# project_X.net
KiCad netlist of a schematic drawn in EAGLE
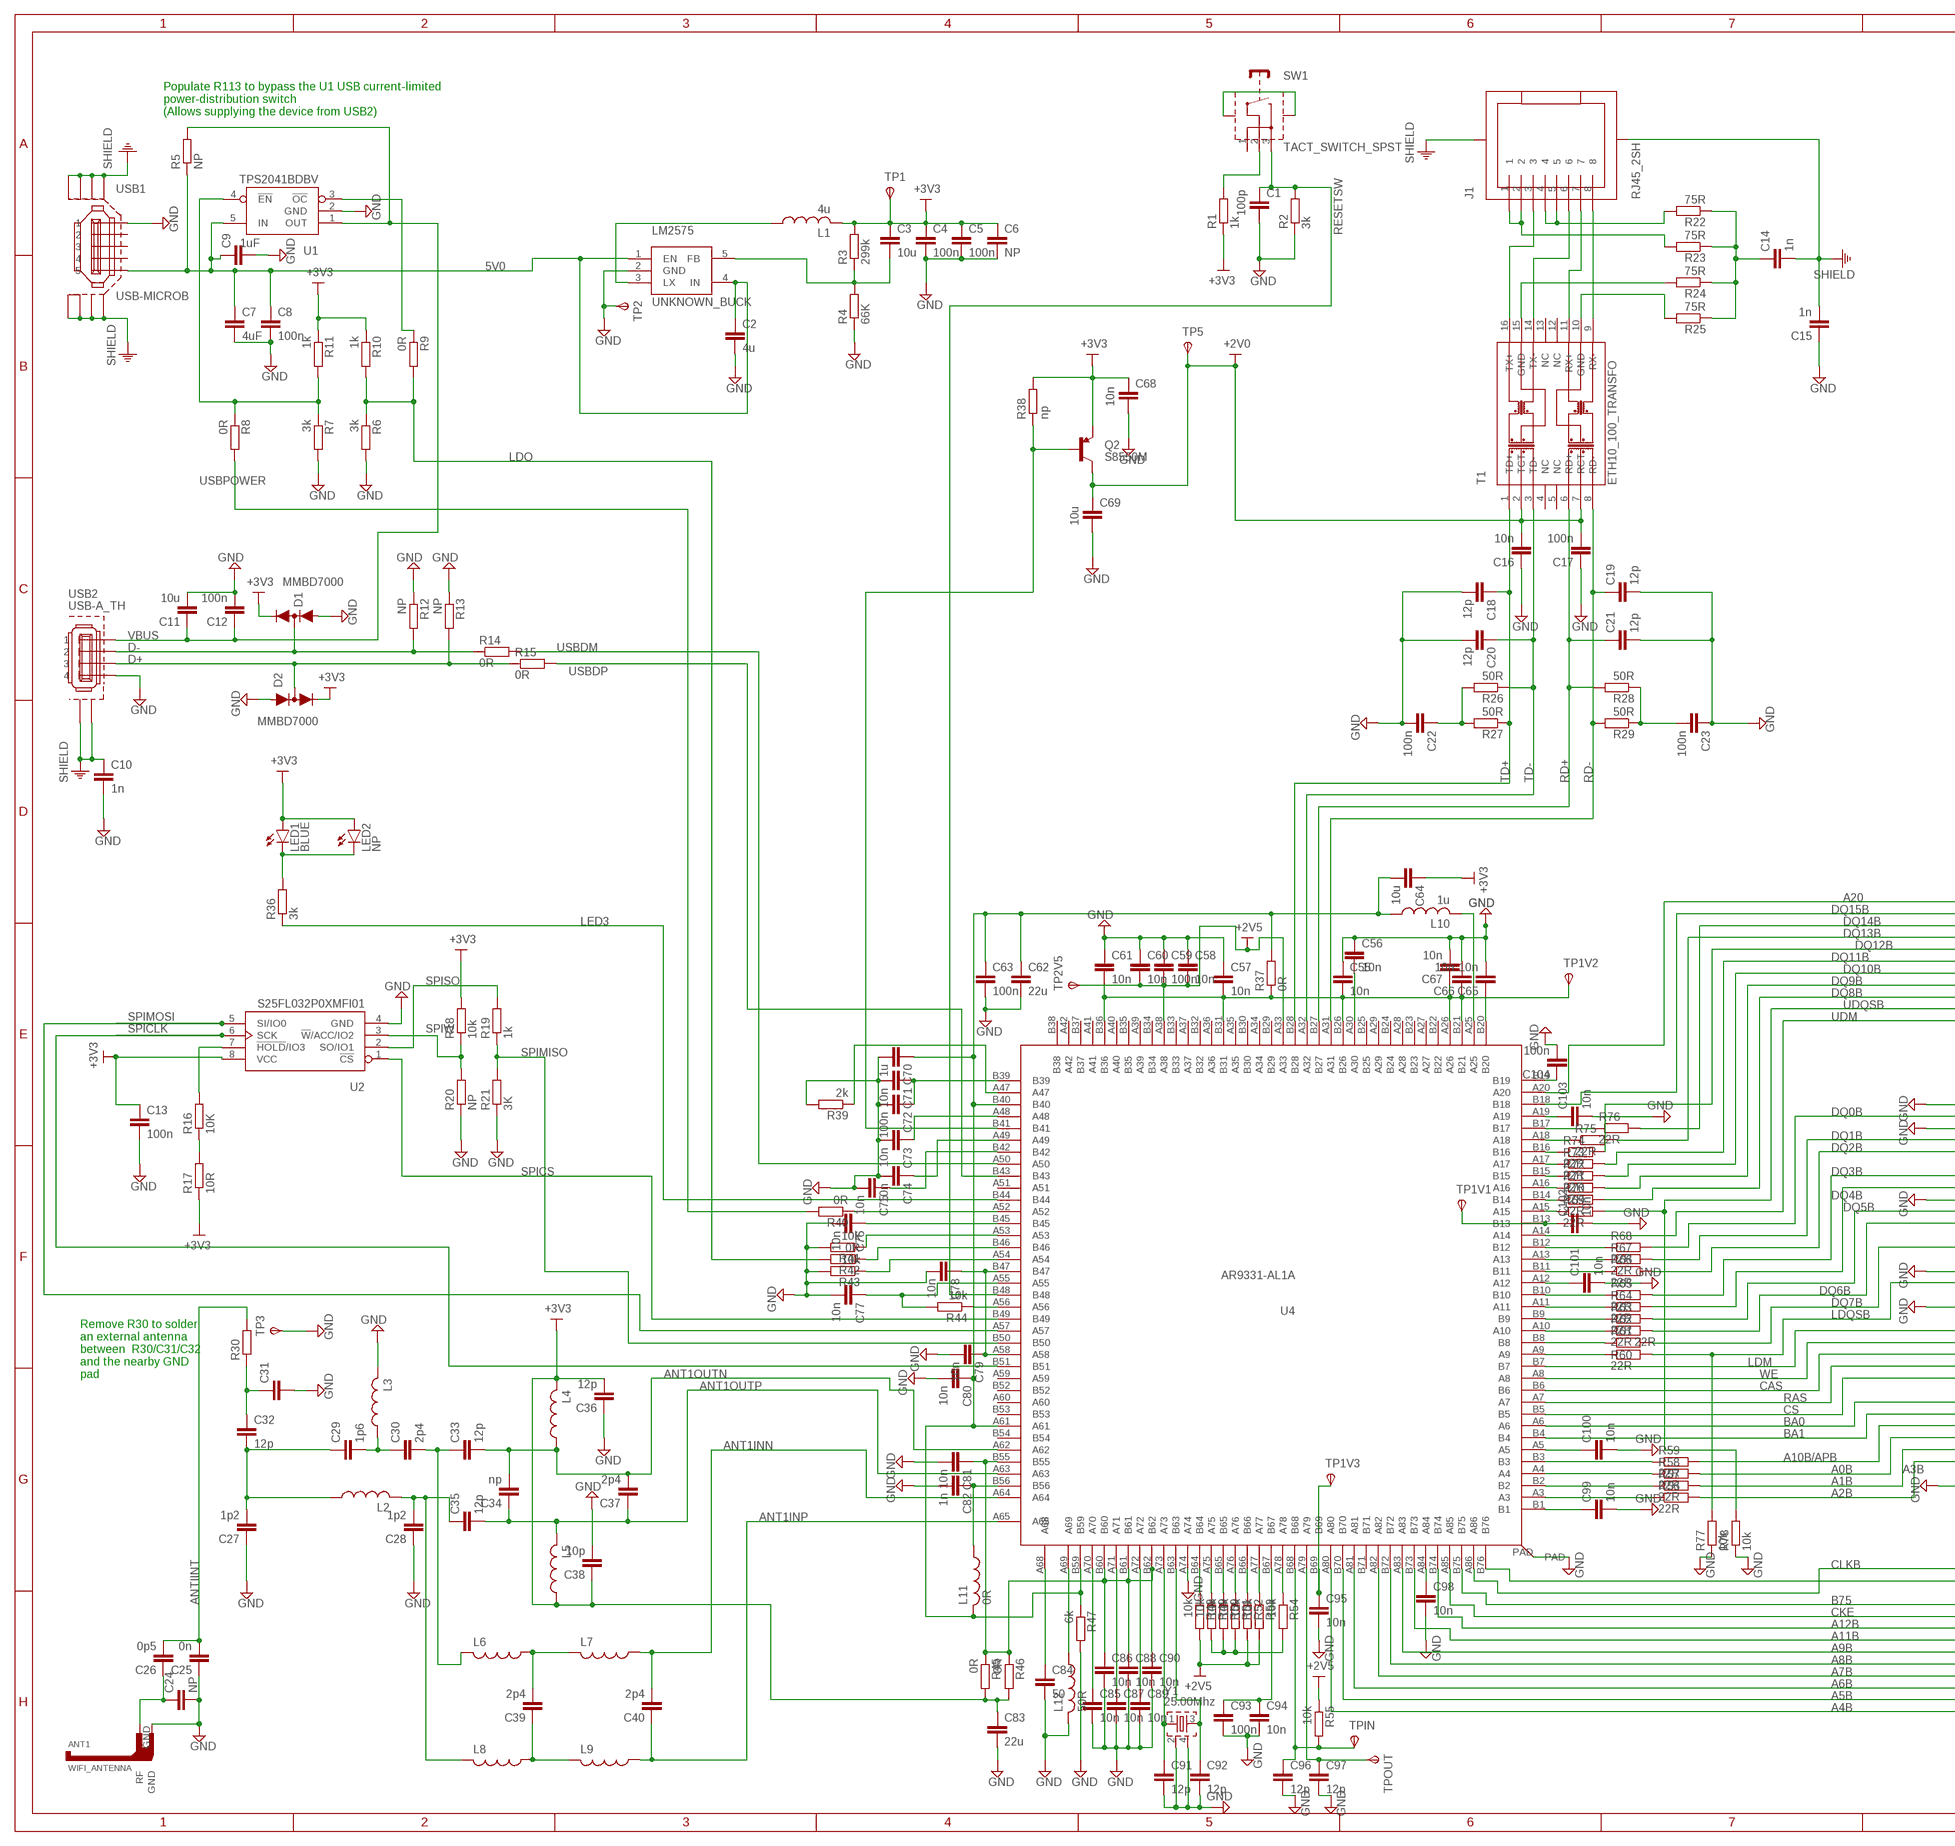
[diagram p0: schematic, sheet 1, part 1 of 2]
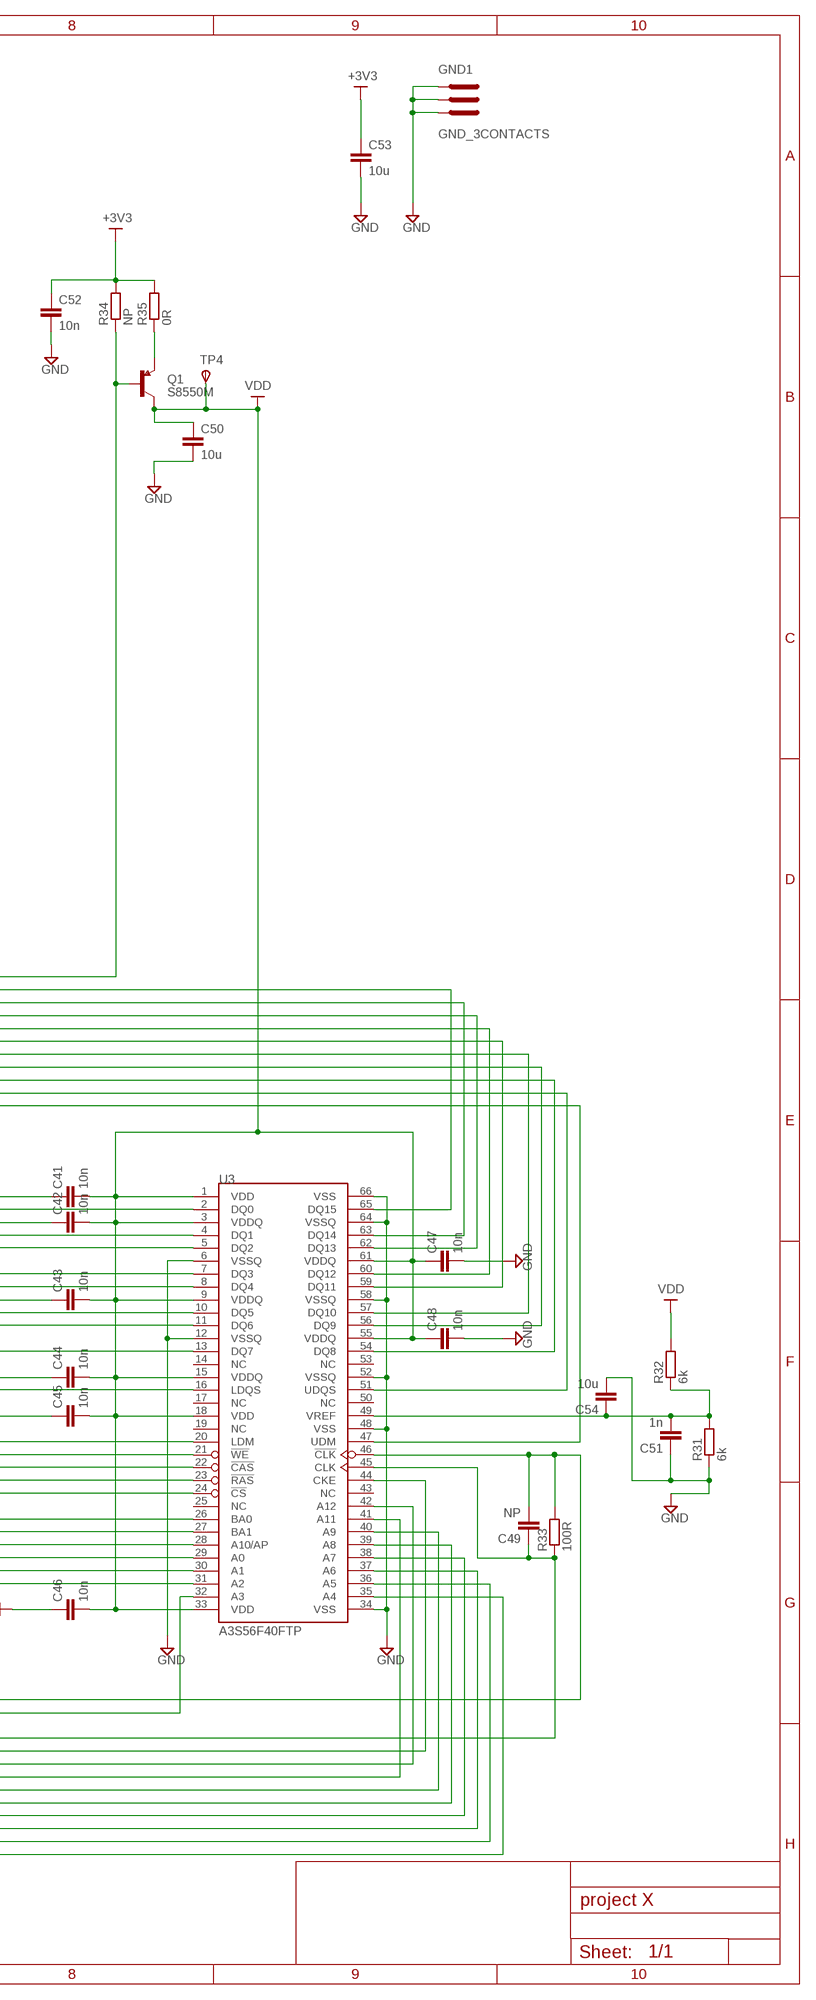
[diagram p1: schematic, sheet 1, part 2 of 2]

(export (version "E")
  (design (tool "Eeschema 10.0.6"))
  (components
    (comp (ref "ANT1")
      (value "WIFI_ANTENNA")
      (footprint "eagle-import:WIFI_ANTENNA")
      (libsource (lib "eagle-import") (part "WIFI_ANTENNA"))
    )
    (comp (ref "C1")
      (value "100p")
      (footprint "eagle-import:C0402")
      (libsource (lib "eagle-import") (part "CAP_0402"))
    )
    (comp (ref "C2")
      (value "4u")
      (footprint "eagle-import:C0603")
      (libsource (lib "eagle-import") (part "CAP_0603"))
    )
    (comp (ref "C3")
      (value "10u")
      (footprint "eagle-import:C0603")
      (libsource (lib "eagle-import") (part "CAP_0603"))
    )
    (comp (ref "C4")
      (value "100n")
      (footprint "eagle-import:C0603")
      (libsource (lib "eagle-import") (part "CAP_0603"))
    )
    (comp (ref "C5")
      (value "100n")
      (footprint "eagle-import:C0603")
      (libsource (lib "eagle-import") (part "CAP_0603"))
    )
    (comp (ref "C6")
      (value "NP")
      (footprint "eagle-import:C0603")
      (libsource (lib "eagle-import") (part "CAP_0603"))
    )
    (comp (ref "C7")
      (value "4uF")
      (footprint "eagle-import:C0603")
      (libsource (lib "eagle-import") (part "CAP_0603"))
    )
    (comp (ref "C8")
      (value "100n")
      (footprint "eagle-import:C0603")
      (libsource (lib "eagle-import") (part "CAP_0603"))
    )
    (comp (ref "C9")
      (value "1uF")
      (footprint "eagle-import:C0603")
      (libsource (lib "eagle-import") (part "CAP_0603"))
    )
    (comp (ref "C10")
      (value "1n")
      (footprint "eagle-import:C0603")
      (libsource (lib "eagle-import") (part "CAP_0603"))
    )
    (comp (ref "C11")
      (value "10u")
      (footprint "eagle-import:C0805")
      (libsource (lib "eagle-import") (part "CAP_0805"))
    )
    (comp (ref "C12")
      (value "100n")
      (footprint "eagle-import:C0805")
      (libsource (lib "eagle-import") (part "CAP_0805"))
    )
    (comp (ref "C13")
      (value "100n")
      (footprint "eagle-import:C0603")
      (libsource (lib "eagle-import") (part "CAP_0603"))
    )
    (comp (ref "C14")
      (value "1n")
      (footprint "eagle-import:C1206")
      (libsource (lib "eagle-import") (part "CAP_1206"))
    )
    (comp (ref "C15")
      (value "1n")
      (footprint "eagle-import:C1206")
      (libsource (lib "eagle-import") (part "CAP_1206"))
    )
    (comp (ref "C16")
      (value "10n")
      (footprint "eagle-import:C1206")
      (libsource (lib "eagle-import") (part "CAP_1206"))
    )
    (comp (ref "C17")
      (value "100n")
      (footprint "eagle-import:C1206")
      (libsource (lib "eagle-import") (part "CAP_1206"))
    )
    (comp (ref "C18")
      (value "12p")
      (footprint "eagle-import:C1206")
      (libsource (lib "eagle-import") (part "CAP_1206"))
    )
    (comp (ref "C19")
      (value "12p")
      (footprint "eagle-import:C1206")
      (libsource (lib "eagle-import") (part "CAP_1206"))
    )
    (comp (ref "C20")
      (value "12p")
      (footprint "eagle-import:C1206")
      (libsource (lib "eagle-import") (part "CAP_1206"))
    )
    (comp (ref "C21")
      (value "12p")
      (footprint "eagle-import:C1206")
      (libsource (lib "eagle-import") (part "CAP_1206"))
    )
    (comp (ref "C22")
      (value "100n")
      (footprint "eagle-import:C1206")
      (libsource (lib "eagle-import") (part "CAP_1206"))
    )
    (comp (ref "C23")
      (value "100n")
      (footprint "eagle-import:C1206")
      (libsource (lib "eagle-import") (part "CAP_1206"))
    )
    (comp (ref "C24")
      (value "NP")
      (footprint "eagle-import:C0603")
      (libsource (lib "eagle-import") (part "CAP_0603"))
    )
    (comp (ref "C25")
      (value "0n")
      (footprint "eagle-import:C0603")
      (libsource (lib "eagle-import") (part "CAP_0603"))
    )
    (comp (ref "C26")
      (value "0p5")
      (footprint "eagle-import:C0603")
      (libsource (lib "eagle-import") (part "CAP_0603"))
    )
    (comp (ref "C27")
      (value "1p2")
      (footprint "eagle-import:C0603")
      (libsource (lib "eagle-import") (part "CAP_0603"))
    )
    (comp (ref "C28")
      (value "1p2")
      (footprint "eagle-import:C0603")
      (libsource (lib "eagle-import") (part "CAP_0603"))
    )
    (comp (ref "C29")
      (value "1p6")
      (footprint "eagle-import:C0603")
      (libsource (lib "eagle-import") (part "CAP_0603"))
    )
    (comp (ref "C30")
      (value "2p4")
      (footprint "eagle-import:C0603")
      (libsource (lib "eagle-import") (part "CAP_0603"))
    )
    (comp (ref "C31")
      (value "CAP_0603")
      (footprint "eagle-import:C0603")
      (libsource (lib "eagle-import") (part "CAP_0603"))
    )
    (comp (ref "C32")
      (value "12p")
      (footprint "eagle-import:C0603")
      (libsource (lib "eagle-import") (part "CAP_0603"))
    )
    (comp (ref "C33")
      (value "12p")
      (footprint "eagle-import:C0603")
      (libsource (lib "eagle-import") (part "CAP_0603"))
    )
    (comp (ref "C34")
      (value "np")
      (footprint "eagle-import:C0603")
      (libsource (lib "eagle-import") (part "CAP_0603"))
    )
    (comp (ref "C35")
      (value "12p")
      (footprint "eagle-import:C0603")
      (libsource (lib "eagle-import") (part "CAP_0603"))
    )
    (comp (ref "C36")
      (value "12p")
      (footprint "eagle-import:C0603")
      (libsource (lib "eagle-import") (part "CAP_0603"))
    )
    (comp (ref "C37")
      (value "2p4")
      (footprint "eagle-import:C0603")
      (libsource (lib "eagle-import") (part "CAP_0603"))
    )
    (comp (ref "C38")
      (value "10p")
      (footprint "eagle-import:C0603")
      (libsource (lib "eagle-import") (part "CAP_0603"))
    )
    (comp (ref "C39")
      (value "2p4")
      (footprint "eagle-import:C0603")
      (libsource (lib "eagle-import") (part "CAP_0603"))
    )
    (comp (ref "C40")
      (value "2p4")
      (footprint "eagle-import:C0603")
      (libsource (lib "eagle-import") (part "CAP_0603"))
    )
    (comp (ref "C41")
      (value "10n")
      (footprint "eagle-import:C0603")
      (libsource (lib "eagle-import") (part "CAP_0603"))
    )
    (comp (ref "C42")
      (value "10n")
      (footprint "eagle-import:C0603")
      (libsource (lib "eagle-import") (part "CAP_0603"))
    )
    (comp (ref "C43")
      (value "10n")
      (footprint "eagle-import:C0603")
      (libsource (lib "eagle-import") (part "CAP_0603"))
    )
    (comp (ref "C44")
      (value "10n")
      (footprint "eagle-import:C0603")
      (libsource (lib "eagle-import") (part "CAP_0603"))
    )
    (comp (ref "C45")
      (value "10n")
      (footprint "eagle-import:C0603")
      (libsource (lib "eagle-import") (part "CAP_0603"))
    )
    (comp (ref "C46")
      (value "10n")
      (footprint "eagle-import:C0603")
      (libsource (lib "eagle-import") (part "CAP_0603"))
    )
    (comp (ref "C47")
      (value "10n")
      (footprint "eagle-import:C0603")
      (libsource (lib "eagle-import") (part "CAP_0603"))
    )
    (comp (ref "C48")
      (value "10n")
      (footprint "eagle-import:C0603")
      (libsource (lib "eagle-import") (part "CAP_0603"))
    )
    (comp (ref "C49")
      (value "NP")
      (footprint "eagle-import:C0603")
      (libsource (lib "eagle-import") (part "CAP_0603"))
    )
    (comp (ref "C50")
      (value "10u")
      (footprint "eagle-import:C0805")
      (libsource (lib "eagle-import") (part "CAP_0805"))
    )
    (comp (ref "C51")
      (value "1n")
      (footprint "eagle-import:C0603")
      (libsource (lib "eagle-import") (part "CAP_0603"))
    )
    (comp (ref "C52")
      (value "10n")
      (footprint "eagle-import:C0603")
      (libsource (lib "eagle-import") (part "CAP_0603"))
    )
    (comp (ref "C53")
      (value "10u")
      (footprint "eagle-import:C0805")
      (libsource (lib "eagle-import") (part "CAP_0805"))
    )
    (comp (ref "C54")
      (value "10u")
      (footprint "eagle-import:C0805")
      (libsource (lib "eagle-import") (part "CAP_0805"))
    )
    (comp (ref "C55")
      (value "10n")
      (footprint "eagle-import:C0805")
      (libsource (lib "eagle-import") (part "CAP_0805"))
    )
    (comp (ref "C56")
      (value "10n")
      (footprint "eagle-import:C0805")
      (libsource (lib "eagle-import") (part "CAP_0805"))
    )
    (comp (ref "C57")
      (value "10n")
      (footprint "eagle-import:C0805")
      (libsource (lib "eagle-import") (part "CAP_0805"))
    )
    (comp (ref "C58")
      (value "10n")
      (footprint "eagle-import:C0805")
      (libsource (lib "eagle-import") (part "CAP_0805"))
    )
    (comp (ref "C59")
      (value "100n")
      (footprint "eagle-import:C0805")
      (libsource (lib "eagle-import") (part "CAP_0805"))
    )
    (comp (ref "C60")
      (value "10n")
      (footprint "eagle-import:C0805")
      (libsource (lib "eagle-import") (part "CAP_0805"))
    )
    (comp (ref "C61")
      (value "10n")
      (footprint "eagle-import:C0805")
      (libsource (lib "eagle-import") (part "CAP_0805"))
    )
    (comp (ref "C62")
      (value "22u")
      (footprint "eagle-import:C0805")
      (libsource (lib "eagle-import") (part "CAP_0805"))
    )
    (comp (ref "C63")
      (value "100n")
      (footprint "eagle-import:C0805")
      (libsource (lib "eagle-import") (part "CAP_0805"))
    )
    (comp (ref "C64")
      (value "10u")
      (footprint "eagle-import:C0805")
      (libsource (lib "eagle-import") (part "CAP_0805"))
    )
    (comp (ref "C65")
      (value "10n")
      (footprint "eagle-import:C0805")
      (libsource (lib "eagle-import") (part "CAP_0805"))
    )
    (comp (ref "C66")
      (value "10n")
      (footprint "eagle-import:C0805")
      (libsource (lib "eagle-import") (part "CAP_0805"))
    )
    (comp (ref "C67")
      (value "10n")
      (footprint "eagle-import:C0805")
      (libsource (lib "eagle-import") (part "CAP_0805"))
    )
    (comp (ref "C68")
      (value "10n")
      (footprint "eagle-import:C0402")
      (libsource (lib "eagle-import") (part "CAP_0402"))
    )
    (comp (ref "C69")
      (value "10u")
      (footprint "eagle-import:C0402")
      (libsource (lib "eagle-import") (part "CAP_0402"))
    )
    (comp (ref "C70")
      (value "1u")
      (footprint "eagle-import:C0603")
      (libsource (lib "eagle-import") (part "CAP_0603"))
    )
    (comp (ref "C71")
      (value "10n")
      (footprint "eagle-import:C0603")
      (libsource (lib "eagle-import") (part "CAP_0603"))
    )
    (comp (ref "C72")
      (value "100n")
      (footprint "eagle-import:C0603")
      (libsource (lib "eagle-import") (part "CAP_0603"))
    )
    (comp (ref "C73")
      (value "10n")
      (footprint "eagle-import:C0603")
      (libsource (lib "eagle-import") (part "CAP_0603"))
    )
    (comp (ref "C74")
      (value "10n")
      (footprint "eagle-import:C0603")
      (libsource (lib "eagle-import") (part "CAP_0603"))
    )
    (comp (ref "C75")
      (value "10n")
      (footprint "eagle-import:C0603")
      (libsource (lib "eagle-import") (part "CAP_0603"))
    )
    (comp (ref "C76")
      (value "10n")
      (footprint "eagle-import:C0603")
      (libsource (lib "eagle-import") (part "CAP_0603"))
    )
    (comp (ref "C77")
      (value "10n")
      (footprint "eagle-import:C0603")
      (libsource (lib "eagle-import") (part "CAP_0603"))
    )
    (comp (ref "C78")
      (value "10n")
      (footprint "eagle-import:C0603")
      (libsource (lib "eagle-import") (part "CAP_0603"))
    )
    (comp (ref "C79")
      (value "10n")
      (footprint "eagle-import:C0603")
      (libsource (lib "eagle-import") (part "CAP_0603"))
    )
    (comp (ref "C80")
      (value "10n")
      (footprint "eagle-import:C0603")
      (libsource (lib "eagle-import") (part "CAP_0603"))
    )
    (comp (ref "C81")
      (value "10n")
      (footprint "eagle-import:C0603")
      (libsource (lib "eagle-import") (part "CAP_0603"))
    )
    (comp (ref "C82")
      (value "1n")
      (footprint "eagle-import:C0603")
      (libsource (lib "eagle-import") (part "CAP_0603"))
    )
    (comp (ref "C83")
      (value "22u")
      (footprint "eagle-import:C0603")
      (libsource (lib "eagle-import") (part "CAP_0603"))
    )
    (comp (ref "C84")
      (value "50")
      (footprint "eagle-import:C0603")
      (libsource (lib "eagle-import") (part "CAP_0603"))
    )
    (comp (ref "C85")
      (value "10n")
      (footprint "eagle-import:C0603")
      (libsource (lib "eagle-import") (part "CAP_0603"))
    )
    (comp (ref "C86")
      (value "10n")
      (footprint "eagle-import:C0603")
      (libsource (lib "eagle-import") (part "CAP_0603"))
    )
    (comp (ref "C87")
      (value "10n")
      (footprint "eagle-import:C0603")
      (libsource (lib "eagle-import") (part "CAP_0603"))
    )
    (comp (ref "C88")
      (value "10n")
      (footprint "eagle-import:C0603")
      (libsource (lib "eagle-import") (part "CAP_0603"))
    )
    (comp (ref "C89")
      (value "10n")
      (footprint "eagle-import:C0603")
      (libsource (lib "eagle-import") (part "CAP_0603"))
    )
    (comp (ref "C90")
      (value "10n")
      (footprint "eagle-import:C0603")
      (libsource (lib "eagle-import") (part "CAP_0603"))
    )
    (comp (ref "C91")
      (value "12p")
      (footprint "eagle-import:C0603")
      (libsource (lib "eagle-import") (part "CAP_0603"))
    )
    (comp (ref "C92")
      (value "12p")
      (footprint "eagle-import:C0603")
      (libsource (lib "eagle-import") (part "CAP_0603"))
    )
    (comp (ref "C93")
      (value "100n")
      (footprint "eagle-import:C0603")
      (libsource (lib "eagle-import") (part "CAP_0603"))
    )
    (comp (ref "C94")
      (value "10n")
      (footprint "eagle-import:C0603")
      (libsource (lib "eagle-import") (part "CAP_0603"))
    )
    (comp (ref "C95")
      (value "10n")
      (footprint "eagle-import:C0603")
      (libsource (lib "eagle-import") (part "CAP_0603"))
    )
    (comp (ref "C96")
      (value "12p")
      (footprint "eagle-import:C0603")
      (libsource (lib "eagle-import") (part "CAP_0603"))
    )
    (comp (ref "C97")
      (value "12p")
      (footprint "eagle-import:C0603")
      (libsource (lib "eagle-import") (part "CAP_0603"))
    )
    (comp (ref "C98")
      (value "10n")
      (footprint "eagle-import:C0603")
      (libsource (lib "eagle-import") (part "CAP_0603"))
    )
    (comp (ref "C99")
      (value "10n")
      (footprint "eagle-import:C0603")
      (libsource (lib "eagle-import") (part "CAP_0603"))
    )
    (comp (ref "C100")
      (value "10n")
      (footprint "eagle-import:C0603")
      (libsource (lib "eagle-import") (part "CAP_0603"))
    )
    (comp (ref "C101")
      (value "10n")
      (footprint "eagle-import:C0603")
      (libsource (lib "eagle-import") (part "CAP_0603"))
    )
    (comp (ref "C102")
      (value "10n")
      (footprint "eagle-import:C0603")
      (libsource (lib "eagle-import") (part "CAP_0603"))
    )
    (comp (ref "C103")
      (value "10n")
      (footprint "eagle-import:C0603")
      (libsource (lib "eagle-import") (part "CAP_0603"))
    )
    (comp (ref "C104")
      (value "100n")
      (footprint "eagle-import:C0603")
      (libsource (lib "eagle-import") (part "CAP_0603"))
    )
    (comp (ref "D1")
      (value "MMBD7000")
      (footprint "eagle-import:SOT23-3")
      (libsource (lib "eagle-import") (part "MMBD7000"))
    )
    (comp (ref "D2")
      (value "MMBD7000")
      (footprint "eagle-import:SOT23-3")
      (libsource (lib "eagle-import") (part "MMBD7000"))
    )
    (comp (ref "GND1")
      (value "GND_3CONTACTS")
      (footprint "eagle-import:GND_3CONTACT")
      (libsource (lib "eagle-import") (part "GND_3CONTACTS"))
    )
    (comp (ref "J1")
      (value "RJ45_2SH")
      (footprint "eagle-import:RJ45_LP_RA_SMT")
      (libsource (lib "eagle-import") (part "RJ45_2SH"))
    )
    (comp (ref "L1")
      (value "4u")
      (footprint "eagle-import:L0402")
      (libsource (lib "eagle-import") (part "IND_0402"))
    )
    (comp (ref "L2")
      (value "IND_0402")
      (footprint "eagle-import:L0402")
      (libsource (lib "eagle-import") (part "IND_0402"))
    )
    (comp (ref "L3")
      (value "IND_0402")
      (footprint "eagle-import:L0402")
      (libsource (lib "eagle-import") (part "IND_0402"))
    )
    (comp (ref "L4")
      (value "IND_0402")
      (footprint "eagle-import:L0402")
      (libsource (lib "eagle-import") (part "IND_0402"))
    )
    (comp (ref "L5")
      (value "IND_0402")
      (footprint "eagle-import:L0402")
      (libsource (lib "eagle-import") (part "IND_0402"))
    )
    (comp (ref "L6")
      (value "IND_0402")
      (footprint "eagle-import:L0402")
      (libsource (lib "eagle-import") (part "IND_0402"))
    )
    (comp (ref "L7")
      (value "IND_0402")
      (footprint "eagle-import:L0402")
      (libsource (lib "eagle-import") (part "IND_0402"))
    )
    (comp (ref "L8")
      (value "IND_0402")
      (footprint "eagle-import:L0402")
      (libsource (lib "eagle-import") (part "IND_0402"))
    )
    (comp (ref "L9")
      (value "IND_0402")
      (footprint "eagle-import:L0402")
      (libsource (lib "eagle-import") (part "IND_0402"))
    )
    (comp (ref "L10")
      (value "1u")
      (footprint "eagle-import:L1008")
      (libsource (lib "eagle-import") (part "IND_1008"))
    )
    (comp (ref "L11")
      (value "0R")
      (footprint "eagle-import:L0402")
      (libsource (lib "eagle-import") (part "IND_0402"))
    )
    (comp (ref "L12")
      (value "50R")
      (footprint "eagle-import:L0402")
      (libsource (lib "eagle-import") (part "IND_0402"))
    )
    (comp (ref "LED1")
      (value "BLUE")
      (footprint "eagle-import:LED3MM")
      (libsource (lib "eagle-import") (part "LED_3MM"))
    )
    (comp (ref "LED2")
      (value "NP")
      (footprint "eagle-import:LED3MM")
      (libsource (lib "eagle-import") (part "LED_3MM"))
    )
    (comp (ref "LM2575")
      (value "UNKNOWN_BUCK")
      (footprint "eagle-import:SOT23-5")
      (libsource (lib "eagle-import") (part "UNKNOWN_BUCK"))
    )
    (comp (ref "Q1")
      (value "S8550M")
      (footprint "eagle-import:SOT23-3")
      (libsource (lib "eagle-import") (part "TRANSISTOR_PNP"))
    )
    (comp (ref "Q2")
      (value "S8550M")
      (footprint "eagle-import:SOT23-3")
      (libsource (lib "eagle-import") (part "TRANSISTOR_PNP"))
    )
    (comp (ref "R1")
      (value "1k")
      (footprint "eagle-import:R0402")
      (libsource (lib "eagle-import") (part "RES_0402"))
    )
    (comp (ref "R2")
      (value "3k")
      (footprint "eagle-import:R0402")
      (libsource (lib "eagle-import") (part "RES_0402"))
    )
    (comp (ref "R3")
      (value "299k")
      (footprint "eagle-import:R0603")
      (libsource (lib "eagle-import") (part "RES_0603"))
    )
    (comp (ref "R4")
      (value "66K")
      (footprint "eagle-import:R0603")
      (libsource (lib "eagle-import") (part "RES_0603"))
    )
    (comp (ref "R5")
      (value "NP")
      (footprint "eagle-import:R0603")
      (libsource (lib "eagle-import") (part "RES_0603"))
    )
    (comp (ref "R6")
      (value "3k")
      (footprint "eagle-import:R0603")
      (libsource (lib "eagle-import") (part "RES_0603"))
    )
    (comp (ref "R7")
      (value "3k")
      (footprint "eagle-import:R0603")
      (libsource (lib "eagle-import") (part "RES_0603"))
    )
    (comp (ref "R8")
      (value "0R")
      (footprint "eagle-import:R0603")
      (libsource (lib "eagle-import") (part "RES_0603"))
    )
    (comp (ref "R9")
      (value "0R")
      (footprint "eagle-import:R0603")
      (libsource (lib "eagle-import") (part "RES_0603"))
    )
    (comp (ref "R10")
      (value "1k")
      (footprint "eagle-import:R0603")
      (libsource (lib "eagle-import") (part "RES_0603"))
    )
    (comp (ref "R11")
      (value "1k")
      (footprint "eagle-import:R0603")
      (libsource (lib "eagle-import") (part "RES_0603"))
    )
    (comp (ref "R12")
      (value "NP")
      (footprint "eagle-import:R0603")
      (libsource (lib "eagle-import") (part "RES_0603"))
    )
    (comp (ref "R13")
      (value "NP")
      (footprint "eagle-import:R0603")
      (libsource (lib "eagle-import") (part "RES_0603"))
    )
    (comp (ref "R14")
      (value "0R")
      (footprint "eagle-import:R0603")
      (libsource (lib "eagle-import") (part "RES_0603"))
    )
    (comp (ref "R15")
      (value "0R")
      (footprint "eagle-import:R0603")
      (libsource (lib "eagle-import") (part "RES_0603"))
    )
    (comp (ref "R16")
      (value "10K")
      (footprint "eagle-import:R0603")
      (libsource (lib "eagle-import") (part "RES_0603"))
    )
    (comp (ref "R17")
      (value "10R")
      (footprint "eagle-import:R0603")
      (libsource (lib "eagle-import") (part "RES_0603"))
    )
    (comp (ref "R18")
      (value "10k")
      (footprint "eagle-import:R0603")
      (libsource (lib "eagle-import") (part "RES_0603"))
    )
    (comp (ref "R19")
      (value "1k")
      (footprint "eagle-import:R0603")
      (libsource (lib "eagle-import") (part "RES_0603"))
    )
    (comp (ref "R20")
      (value "NP")
      (footprint "eagle-import:R0603")
      (libsource (lib "eagle-import") (part "RES_0603"))
    )
    (comp (ref "R21")
      (value "3K")
      (footprint "eagle-import:R0603")
      (libsource (lib "eagle-import") (part "RES_0603"))
    )
    (comp (ref "R22")
      (value "75R")
      (footprint "eagle-import:R0402")
      (libsource (lib "eagle-import") (part "RES_0402"))
    )
    (comp (ref "R23")
      (value "75R")
      (footprint "eagle-import:R0402")
      (libsource (lib "eagle-import") (part "RES_0402"))
    )
    (comp (ref "R24")
      (value "75R")
      (footprint "eagle-import:R0402")
      (libsource (lib "eagle-import") (part "RES_0402"))
    )
    (comp (ref "R25")
      (value "75R")
      (footprint "eagle-import:R0402")
      (libsource (lib "eagle-import") (part "RES_0402"))
    )
    (comp (ref "R26")
      (value "50R")
      (footprint "eagle-import:R0402")
      (libsource (lib "eagle-import") (part "RES_0402"))
    )
    (comp (ref "R27")
      (value "50R")
      (footprint "eagle-import:R0402")
      (libsource (lib "eagle-import") (part "RES_0402"))
    )
    (comp (ref "R28")
      (value "50R")
      (footprint "eagle-import:R0402")
      (libsource (lib "eagle-import") (part "RES_0402"))
    )
    (comp (ref "R29")
      (value "50R")
      (footprint "eagle-import:R0402")
      (libsource (lib "eagle-import") (part "RES_0402"))
    )
    (comp (ref "R30")
      (value "RES_0603")
      (footprint "eagle-import:R0603")
      (libsource (lib "eagle-import") (part "RES_0603"))
    )
    (comp (ref "R31")
      (value "6k")
      (footprint "eagle-import:R0603")
      (libsource (lib "eagle-import") (part "RES_0603"))
    )
    (comp (ref "R32")
      (value "6k")
      (footprint "eagle-import:R0603")
      (libsource (lib "eagle-import") (part "RES_0603"))
    )
    (comp (ref "R33")
      (value "100R")
      (footprint "eagle-import:R0603")
      (libsource (lib "eagle-import") (part "RES_0603"))
    )
    (comp (ref "R34")
      (value "NP")
      (footprint "eagle-import:R0603")
      (libsource (lib "eagle-import") (part "RES_0603"))
    )
    (comp (ref "R35")
      (value "0R")
      (footprint "eagle-import:R0603")
      (libsource (lib "eagle-import") (part "RES_0603"))
    )
    (comp (ref "R36")
      (value "3k")
      (footprint "eagle-import:R0603")
      (libsource (lib "eagle-import") (part "RES_0603"))
    )
    (comp (ref "R37")
      (value "0R")
      (footprint "eagle-import:R0603")
      (libsource (lib "eagle-import") (part "RES_0603"))
    )
    (comp (ref "R38")
      (value "np")
      (footprint "eagle-import:R0603")
      (libsource (lib "eagle-import") (part "RES_0603"))
    )
    (comp (ref "R39")
      (value "2k")
      (footprint "eagle-import:R0603")
      (libsource (lib "eagle-import") (part "RES_0603"))
    )
    (comp (ref "R40")
      (value "0R")
      (footprint "eagle-import:R0603")
      (libsource (lib "eagle-import") (part "RES_0603"))
    )
    (comp (ref "R41")
      (value "10k")
      (footprint "eagle-import:R0603")
      (libsource (lib "eagle-import") (part "RES_0603"))
    )
    (comp (ref "R42")
      (value "0R")
      (footprint "eagle-import:R0603")
      (libsource (lib "eagle-import") (part "RES_0603"))
    )
    (comp (ref "R43")
      (value "10k")
      (footprint "eagle-import:R0603")
      (libsource (lib "eagle-import") (part "RES_0603"))
    )
    (comp (ref "R44")
      (value "10k")
      (footprint "eagle-import:R0603")
      (libsource (lib "eagle-import") (part "RES_0603"))
    )
    (comp (ref "R45")
      (value "0R")
      (footprint "eagle-import:R0603")
      (libsource (lib "eagle-import") (part "RES_0603"))
    )
    (comp (ref "R46")
      (value "0R")
      (footprint "eagle-import:R0603")
      (libsource (lib "eagle-import") (part "RES_0603"))
    )
    (comp (ref "R47")
      (value "6k")
      (footprint "eagle-import:R0603")
      (libsource (lib "eagle-import") (part "RES_0603"))
    )
    (comp (ref "R48")
      (value "10k")
      (footprint "eagle-import:R0603")
      (libsource (lib "eagle-import") (part "RES_0603"))
    )
    (comp (ref "R49")
      (value "10k")
      (footprint "eagle-import:R0603")
      (libsource (lib "eagle-import") (part "RES_0603"))
    )
    (comp (ref "R50")
      (value "10k")
      (footprint "eagle-import:R0603")
      (libsource (lib "eagle-import") (part "RES_0603"))
    )
    (comp (ref "R51")
      (value "10k")
      (footprint "eagle-import:R0603")
      (libsource (lib "eagle-import") (part "RES_0603"))
    )
    (comp (ref "R52")
      (value "10k")
      (footprint "eagle-import:R0603")
      (libsource (lib "eagle-import") (part "RES_0603"))
    )
    (comp (ref "R53")
      (value "10k")
      (footprint "eagle-import:R0603")
      (libsource (lib "eagle-import") (part "RES_0603"))
    )
    (comp (ref "R54")
      (value "10k")
      (footprint "eagle-import:R0603")
      (libsource (lib "eagle-import") (part "RES_0603"))
    )
    (comp (ref "R55")
      (value "10k")
      (footprint "eagle-import:R0603")
      (libsource (lib "eagle-import") (part "RES_0603"))
    )
    (comp (ref "R56")
      (value "22R")
      (footprint "eagle-import:R0603")
      (libsource (lib "eagle-import") (part "RES_0603"))
    )
    (comp (ref "R57")
      (value "22R")
      (footprint "eagle-import:R0603")
      (libsource (lib "eagle-import") (part "RES_0603"))
    )
    (comp (ref "R58")
      (value "22R")
      (footprint "eagle-import:R0603")
      (libsource (lib "eagle-import") (part "RES_0603"))
    )
    (comp (ref "R59")
      (value "22R")
      (footprint "eagle-import:R0603")
      (libsource (lib "eagle-import") (part "RES_0603"))
    )
    (comp (ref "R60")
      (value "22R")
      (footprint "eagle-import:R0603")
      (libsource (lib "eagle-import") (part "RES_0603"))
    )
    (comp (ref "R61")
      (value "22R")
      (footprint "eagle-import:R0603")
      (libsource (lib "eagle-import") (part "RES_0603"))
    )
    (comp (ref "R62")
      (value "22R")
      (footprint "eagle-import:R0603")
      (libsource (lib "eagle-import") (part "RES_0603"))
    )
    (comp (ref "R63")
      (value "22R")
      (footprint "eagle-import:R0603")
      (libsource (lib "eagle-import") (part "RES_0603"))
    )
    (comp (ref "R64")
      (value "22R")
      (footprint "eagle-import:R0603")
      (libsource (lib "eagle-import") (part "RES_0603"))
    )
    (comp (ref "R65")
      (value "22R")
      (footprint "eagle-import:R0603")
      (libsource (lib "eagle-import") (part "RES_0603"))
    )
    (comp (ref "R66")
      (value "22R")
      (footprint "eagle-import:R0603")
      (libsource (lib "eagle-import") (part "RES_0603"))
    )
    (comp (ref "R67")
      (value "22R")
      (footprint "eagle-import:R0603")
      (libsource (lib "eagle-import") (part "RES_0603"))
    )
    (comp (ref "R68")
      (value "22R")
      (footprint "eagle-import:R0603")
      (libsource (lib "eagle-import") (part "RES_0603"))
    )
    (comp (ref "R69")
      (value "22R")
      (footprint "eagle-import:R0603")
      (libsource (lib "eagle-import") (part "RES_0603"))
    )
    (comp (ref "R70")
      (value "22R")
      (footprint "eagle-import:R0603")
      (libsource (lib "eagle-import") (part "RES_0603"))
    )
    (comp (ref "R71")
      (value "22R")
      (footprint "eagle-import:R0603")
      (libsource (lib "eagle-import") (part "RES_0603"))
    )
    (comp (ref "R72")
      (value "22R")
      (footprint "eagle-import:R0603")
      (libsource (lib "eagle-import") (part "RES_0603"))
    )
    (comp (ref "R73")
      (value "22R")
      (footprint "eagle-import:R0603")
      (libsource (lib "eagle-import") (part "RES_0603"))
    )
    (comp (ref "R74")
      (value "22R")
      (footprint "eagle-import:R0603")
      (libsource (lib "eagle-import") (part "RES_0603"))
    )
    (comp (ref "R75")
      (value "22R")
      (footprint "eagle-import:R0603")
      (libsource (lib "eagle-import") (part "RES_0603"))
    )
    (comp (ref "R76")
      (value "22R")
      (footprint "eagle-import:R0603")
      (libsource (lib "eagle-import") (part "RES_0603"))
    )
    (comp (ref "R77")
      (value "10k")
      (footprint "eagle-import:R0603")
      (libsource (lib "eagle-import") (part "RES_0603"))
    )
    (comp (ref "R78")
      (value "10k")
      (footprint "eagle-import:R0603")
      (libsource (lib "eagle-import") (part "RES_0603"))
    )
    (comp (ref "SW1")
      (value "TACT_SWITCH_SPST")
      (footprint "eagle-import:TACT_SWITCH_SPST_RA_SMT")
      (libsource (lib "eagle-import") (part "TACT_SWITCH_SPST"))
    )
    (comp (ref "T1")
      (value "ETH10_100_TRANSFO")
      (footprint "eagle-import:H1601CG")
      (libsource (lib "eagle-import") (part "ETH10_100_TRANSFO"))
    )
    (comp (ref "TP1")
      (value "TEST_PAD")
      (footprint "eagle-import:TEST_PAD")
      (libsource (lib "eagle-import") (part "TEST_PAD"))
    )
    (comp (ref "TP1V1")
      (value "TEST_PAD")
      (footprint "eagle-import:TEST_PAD")
      (libsource (lib "eagle-import") (part "TEST_PAD"))
    )
    (comp (ref "TP1V2")
      (value "TEST_PAD")
      (footprint "eagle-import:TEST_PAD")
      (libsource (lib "eagle-import") (part "TEST_PAD"))
    )
    (comp (ref "TP1V3")
      (value "TEST_PAD")
      (footprint "eagle-import:TEST_PAD")
      (libsource (lib "eagle-import") (part "TEST_PAD"))
    )
    (comp (ref "TP2")
      (value "TEST_PAD")
      (footprint "eagle-import:TEST_PAD")
      (libsource (lib "eagle-import") (part "TEST_PAD"))
    )
    (comp (ref "TP2V5")
      (value "TEST_PAD")
      (footprint "eagle-import:TEST_PAD")
      (libsource (lib "eagle-import") (part "TEST_PAD"))
    )
    (comp (ref "TP3")
      (value "TEST_PAD")
      (footprint "eagle-import:TEST_PAD")
      (libsource (lib "eagle-import") (part "TEST_PAD"))
    )
    (comp (ref "TP4")
      (value "TEST_PAD")
      (footprint "eagle-import:TEST_PAD")
      (libsource (lib "eagle-import") (part "TEST_PAD"))
    )
    (comp (ref "TP5")
      (value "TEST_PAD")
      (footprint "eagle-import:TEST_PAD")
      (libsource (lib "eagle-import") (part "TEST_PAD"))
    )
    (comp (ref "TPIN")
      (value "TEST_PAD")
      (footprint "eagle-import:TEST_PAD")
      (libsource (lib "eagle-import") (part "TEST_PAD"))
    )
    (comp (ref "TPOUT")
      (value "TEST_PAD")
      (footprint "eagle-import:TEST_PAD")
      (libsource (lib "eagle-import") (part "TEST_PAD"))
    )
    (comp (ref "U1")
      (value "TPS2041BDBV")
      (footprint "eagle-import:SOT23-5")
      (libsource (lib "eagle-import") (part "TPS2041BDBV"))
    )
    (comp (ref "U2")
      (value "S25FL032P0XMFI01")
      (footprint "eagle-import:SOP8")
      (libsource (lib "eagle-import") (part "S25FLP0XMFI01032"))
    )
    (comp (ref "U3")
      (value "A3S56F40FTP")
      (footprint "eagle-import:TSOP66")
      (libsource (lib "eagle-import") (part "A3S56FTPF40"))
    )
    (comp (ref "U4")
      (value "AR9331-AL1A")
      (footprint "eagle-import:DRMLF164")
      (libsource (lib "eagle-import") (part "AR9331-AL1A"))
    )
    (comp (ref "USB1")
      (value "USB-MICROB")
      (footprint "eagle-import:USB-MICROB")
      (libsource (lib "eagle-import") (part "USB-MICROB"))
    )
    (comp (ref "USB2")
      (value "USB-A_TH")
      (footprint "eagle-import:USB-A_TH")
      (libsource (lib "eagle-import") (part "USB-A_TH"))
    )
    (comp (ref "Y1")
      (value "25.00Mhz")
      (footprint "eagle-import:CRYSTAL_32_25")
      (libsource (lib "eagle-import") (part "CRYSTAL_2SHIELD"))
    )
  )
  (nets
    (net (code "1") (name "+2V0") (class "Default")
      (node (ref "C16") (pin "2") (pinfunction "2_2") (pintype "passive"))
      (node (ref "C17") (pin "2") (pinfunction "2_2") (pintype "passive"))
      (node (ref "C69") (pin "1") (pinfunction "1_1") (pintype "passive"))
      (node (ref "Q2") (pin "3") (pinfunction "C_3") (pintype "passive"))
      (node (ref "T1") (pin "2") (pinfunction "TCT_2") (pintype "passive"))
      (node (ref "T1") (pin "7") (pinfunction "RCT_7") (pintype "passive"))
      (node (ref "TP5") (pin "1") (pinfunction "PP_1") (pintype "input"))
    )
    (net (code "2") (name "+2V5") (class "Default")
      (node (ref "C58") (pin "2") (pinfunction "2_2") (pintype "passive"))
      (node (ref "C59") (pin "2") (pinfunction "2_2") (pintype "passive"))
      (node (ref "C60") (pin "2") (pinfunction "2_2") (pintype "passive"))
      (node (ref "R48") (pin "2") (pinfunction "2_2") (pintype "passive"))
      (node (ref "R52") (pin "2") (pinfunction "2_2") (pintype "passive"))
      (node (ref "R53") (pin "2") (pinfunction "2_2") (pintype "passive"))
      (node (ref "R55") (pin "1") (pinfunction "1_1") (pintype "passive"))
      (node (ref "TP2V5") (pin "1") (pinfunction "PP_1") (pintype "input"))
      (node (ref "U4") (pin "A33") (pinfunction "A33_A33") (pintype "bidirectional"))
      (node (ref "U4") (pin "A38") (pinfunction "A38_A38") (pintype "bidirectional"))
    )
    (net (code "3") (name "+3V3") (class "Default")
      (node (ref "C13") (pin "1") (pinfunction "1_1") (pintype "passive"))
      (node (ref "C3") (pin "1") (pinfunction "1_1") (pintype "passive"))
      (node (ref "C36") (pin "2") (pinfunction "2_2") (pintype "passive"))
      (node (ref "C38") (pin "1") (pinfunction "1_1") (pintype "passive"))
      (node (ref "C4") (pin "1") (pinfunction "1_1") (pintype "passive"))
      (node (ref "C5") (pin "1") (pinfunction "1_1") (pintype "passive"))
      (node (ref "C52") (pin "1") (pinfunction "1_1") (pintype "passive"))
      (node (ref "C53") (pin "1") (pinfunction "1_1") (pintype "passive"))
      (node (ref "C6") (pin "1") (pinfunction "1_1") (pintype "passive"))
      (node (ref "C64") (pin "1") (pinfunction "1_1") (pintype "passive"))
      (node (ref "C68") (pin "1") (pinfunction "1_1") (pintype "passive"))
      (node (ref "C83") (pin "1") (pinfunction "1_1") (pintype "passive"))
      (node (ref "D1") (pin "2") (pinfunction "C_2") (pintype "passive"))
      (node (ref "D2") (pin "2") (pinfunction "C_2") (pintype "passive"))
      (node (ref "L1") (pin "2") (pinfunction "2_2") (pintype "passive"))
      (node (ref "L4") (pin "2") (pinfunction "2_2") (pintype "passive"))
      (node (ref "L5") (pin "1") (pinfunction "1_1") (pintype "passive"))
      (node (ref "LED1") (pin "A") (pinfunction "A_A") (pintype "passive"))
      (node (ref "LED2") (pin "A") (pinfunction "A_A") (pintype "passive"))
      (node (ref "Q2") (pin "2") (pinfunction "E_2") (pintype "passive"))
      (node (ref "R1") (pin "1") (pinfunction "1_1") (pintype "passive"))
      (node (ref "R10") (pin "1") (pinfunction "1_1") (pintype "passive"))
      (node (ref "R11") (pin "1") (pinfunction "1_1") (pintype "passive"))
      (node (ref "R17") (pin "1") (pinfunction "1_1") (pintype "passive"))
      (node (ref "R18") (pin "2") (pinfunction "2_2") (pintype "passive"))
      (node (ref "R3") (pin "2") (pinfunction "2_2") (pintype "passive"))
      (node (ref "R34") (pin "2") (pinfunction "2_2") (pintype "passive"))
      (node (ref "R35") (pin "2") (pinfunction "2_2") (pintype "passive"))
      (node (ref "R38") (pin "2") (pinfunction "2_2") (pintype "passive"))
      (node (ref "R45") (pin "2") (pinfunction "2_2") (pintype "passive"))
      (node (ref "R46") (pin "2") (pinfunction "2_2") (pintype "passive"))
      (node (ref "TP1") (pin "1") (pinfunction "PP_1") (pintype "input"))
      (node (ref "U2") (pin "8") (pinfunction "VCC_8") (pintype "power_in"))
    )
    (net (code "4") (name "/5V0") (class "Default")
      (node (ref "C2") (pin "1") (pinfunction "1_1") (pintype "passive"))
      (node (ref "C7") (pin "1") (pinfunction "1_1") (pintype "passive"))
      (node (ref "C8") (pin "1") (pinfunction "1_1") (pintype "passive"))
      (node (ref "C9") (pin "1") (pinfunction "1_1") (pintype "passive"))
      (node (ref "LM2575") (pin "1") (pinfunction "EN_1") (pintype "input"))
      (node (ref "LM2575") (pin "4") (pinfunction "IN_4") (pintype "power_in"))
      (node (ref "R5") (pin "1") (pinfunction "1_1") (pintype "passive"))
      (node (ref "U1") (pin "5") (pinfunction "IN_5") (pintype "power_in"))
      (node (ref "USB1") (pin "VBUS") (pinfunction "5_VBUS") (pintype "passive"))
    )
    (net (code "5") (name "/A0B") (class "Default")
      (node (ref "R58") (pin "2") (pinfunction "2_2") (pintype "passive"))
      (node (ref "U3") (pin "29") (pinfunction "A0_29") (pintype "input"))
    )
    (net (code "6") (name "/A1B") (class "Default")
      (node (ref "R57") (pin "2") (pinfunction "2_2") (pintype "passive"))
      (node (ref "U3") (pin "30") (pinfunction "A1_30") (pintype "input"))
    )
    (net (code "7") (name "/A2B") (class "Default")
      (node (ref "R56") (pin "2") (pinfunction "2_2") (pintype "passive"))
      (node (ref "U3") (pin "31") (pinfunction "A2_31") (pintype "input"))
    )
    (net (code "8") (name "/A3B") (class "Default")
      (node (ref "U3") (pin "32") (pinfunction "A3_32") (pintype "input"))
      (node (ref "U4") (pin "B76") (pinfunction "B76_B76") (pintype "bidirectional"))
    )
    (net (code "9") (name "/A4B") (class "Default")
      (node (ref "U3") (pin "35") (pinfunction "A4_35") (pintype "input"))
      (node (ref "U4") (pin "A80") (pinfunction "A80_A80") (pintype "bidirectional"))
    )
    (net (code "10") (name "/A5B") (class "Default")
      (node (ref "U3") (pin "36") (pinfunction "A5_36") (pintype "input"))
      (node (ref "U4") (pin "B70") (pinfunction "B70_B70") (pintype "bidirectional"))
    )
    (net (code "11") (name "/A6B") (class "Default")
      (node (ref "U3") (pin "37") (pinfunction "A6_37") (pintype "input"))
      (node (ref "U4") (pin "A81") (pinfunction "A81_A81") (pintype "bidirectional"))
    )
    (net (code "12") (name "/A7B") (class "Default")
      (node (ref "U3") (pin "38") (pinfunction "A7_38") (pintype "input"))
      (node (ref "U4") (pin "A82") (pinfunction "A82_A82") (pintype "bidirectional"))
    )
    (net (code "13") (name "/A8B") (class "Default")
      (node (ref "U3") (pin "39") (pinfunction "A8_39") (pintype "input"))
      (node (ref "U4") (pin "B72") (pinfunction "B72_B72") (pintype "bidirectional"))
    )
    (net (code "14") (name "/A9B") (class "Default")
      (node (ref "U3") (pin "40") (pinfunction "A9_40") (pintype "input"))
      (node (ref "U4") (pin "A83") (pinfunction "A83_A83") (pintype "bidirectional"))
    )
    (net (code "15") (name "/A10B{slash}APB") (class "Default")
      (node (ref "R59") (pin "2") (pinfunction "2_2") (pintype "passive"))
      (node (ref "U3") (pin "28") (pinfunction "A10/AP_28") (pintype "input"))
    )
    (net (code "16") (name "/A11B") (class "Default")
      (node (ref "U3") (pin "41") (pinfunction "A11_41") (pintype "input"))
      (node (ref "U4") (pin "B73") (pinfunction "B73_B73") (pintype "bidirectional"))
    )
    (net (code "17") (name "/A12B") (class "Default")
      (node (ref "U3") (pin "42") (pinfunction "A12_42") (pintype "input"))
      (node (ref "U4") (pin "B74") (pinfunction "B74_B74") (pintype "bidirectional"))
    )
    (net (code "18") (name "/A20") (class "Default")
      (node (ref "Q1") (pin "1") (pinfunction "B_1") (pintype "passive"))
      (node (ref "R34") (pin "1") (pinfunction "1_1") (pintype "passive"))
      (node (ref "U4") (pin "A20") (pinfunction "A20_A20") (pintype "bidirectional"))
    )
    (net (code "19") (name "/ANT1INN") (class "Default")
      (node (ref "C40") (pin "2") (pinfunction "2_2") (pintype "passive"))
      (node (ref "L7") (pin "1") (pinfunction "1_1") (pintype "passive"))
      (node (ref "U4") (pin "A64") (pinfunction "A64_A64") (pintype "bidirectional"))
    )
    (net (code "20") (name "/ANT1INP") (class "Default")
      (node (ref "C40") (pin "1") (pinfunction "1_1") (pintype "passive"))
      (node (ref "L9") (pin "1") (pinfunction "1_1") (pintype "passive"))
      (node (ref "U4") (pin "A65") (pinfunction "A65_A65") (pintype "bidirectional"))
    )
    (net (code "21") (name "/ANT1OUTN") (class "Default")
      (node (ref "C33") (pin "2") (pinfunction "2_2") (pintype "passive"))
      (node (ref "C34") (pin "2") (pinfunction "2_2") (pintype "passive"))
      (node (ref "C37") (pin "2") (pinfunction "2_2") (pintype "passive"))
      (node (ref "L4") (pin "1") (pinfunction "1_1") (pintype "passive"))
      (node (ref "U4") (pin "A62") (pinfunction "A62_A62") (pintype "bidirectional"))
    )
    (net (code "22") (name "/ANT1OUTP") (class "Default")
      (node (ref "C34") (pin "1") (pinfunction "1_1") (pintype "passive"))
      (node (ref "C35") (pin "2") (pinfunction "2_2") (pintype "passive"))
      (node (ref "C37") (pin "1") (pinfunction "1_1") (pintype "passive"))
      (node (ref "L5") (pin "2") (pinfunction "2_2") (pintype "passive"))
      (node (ref "U4") (pin "A63") (pinfunction "A63_A63") (pintype "bidirectional"))
    )
    (net (code "23") (name "/ANTIINT") (class "Default")
      (node (ref "C25") (pin "2") (pinfunction "2_2") (pintype "passive"))
      (node (ref "C26") (pin "2") (pinfunction "2_2") (pintype "passive"))
      (node (ref "R30") (pin "2") (pinfunction "2_2") (pintype "passive"))
    )
    (net (code "24") (name "/B75") (class "Default")
      (node (ref "C49") (pin "1") (pinfunction "1_1") (pintype "passive"))
      (node (ref "R33") (pin "1") (pinfunction "1_1") (pintype "passive"))
      (node (ref "U3") (pin "45") (pinfunction "CLK_45") (pintype "input"))
      (node (ref "U4") (pin "B75") (pinfunction "B75_B75") (pintype "bidirectional"))
    )
    (net (code "25") (name "/BA0") (class "Default")
      (node (ref "U3") (pin "26") (pinfunction "BA0_26") (pintype "input"))
      (node (ref "U4") (pin "A6") (pinfunction "A6_A6") (pintype "bidirectional"))
    )
    (net (code "26") (name "/BA1") (class "Default")
      (node (ref "U3") (pin "27") (pinfunction "BA1_27") (pintype "input"))
      (node (ref "U4") (pin "B4") (pinfunction "B4_B4") (pintype "bidirectional"))
    )
    (net (code "27") (name "/CAS") (class "Default")
      (node (ref "U3") (pin "22") (pinfunction "~{CAS}_22") (pintype "input"))
      (node (ref "U4") (pin "B6") (pinfunction "B6_B6") (pintype "bidirectional"))
    )
    (net (code "28") (name "/CKE") (class "Default")
      (node (ref "U3") (pin "44") (pinfunction "CKE_44") (pintype "input"))
      (node (ref "U4") (pin "A85") (pinfunction "A85_A85") (pintype "bidirectional"))
    )
    (net (code "29") (name "/CLKB") (class "Default")
      (node (ref "C49") (pin "2") (pinfunction "2_2") (pintype "passive"))
      (node (ref "R33") (pin "2") (pinfunction "2_2") (pintype "passive"))
      (node (ref "U3") (pin "46") (pinfunction "~{CLK}_46") (pintype "input"))
      (node (ref "U4") (pin "A86") (pinfunction "A86_A86") (pintype "bidirectional"))
    )
    (net (code "30") (name "/CS") (class "Default")
      (node (ref "U3") (pin "24") (pinfunction "~{CS}_24") (pintype "input"))
      (node (ref "U4") (pin "B5") (pinfunction "B5_B5") (pintype "bidirectional"))
    )
    (net (code "31") (name "/D+") (class "Default")
      (node (ref "D2") (pin "3") (pinfunction "M_3") (pintype "passive"))
      (node (ref "R13") (pin "2") (pinfunction "2_2") (pintype "passive"))
      (node (ref "R15") (pin "1") (pinfunction "1_1") (pintype "passive"))
      (node (ref "USB2") (pin "3") (pinfunction "3_3") (pintype "passive"))
    )
    (net (code "32") (name "/D-") (class "Default")
      (node (ref "D1") (pin "3") (pinfunction "M_3") (pintype "passive"))
      (node (ref "R12") (pin "2") (pinfunction "2_2") (pintype "passive"))
      (node (ref "R14") (pin "1") (pinfunction "1_1") (pintype "passive"))
      (node (ref "USB2") (pin "2") (pinfunction "2_2") (pintype "passive"))
    )
    (net (code "33") (name "/DQ0B") (class "Default")
      (node (ref "R68") (pin "2") (pinfunction "2_2") (pintype "passive"))
      (node (ref "U3") (pin "2") (pinfunction "DQ0_2") (pintype "bidirectional"))
    )
    (net (code "34") (name "/DQ1B") (class "Default")
      (node (ref "R67") (pin "2") (pinfunction "2_2") (pintype "passive"))
      (node (ref "U3") (pin "4") (pinfunction "DQ1_4") (pintype "bidirectional"))
    )
    (net (code "35") (name "/DQ2B") (class "Default")
      (node (ref "R66") (pin "2") (pinfunction "2_2") (pintype "passive"))
      (node (ref "U3") (pin "5") (pinfunction "DQ2_5") (pintype "bidirectional"))
    )
    (net (code "36") (name "/DQ3B") (class "Default")
      (node (ref "R65") (pin "2") (pinfunction "2_2") (pintype "passive"))
      (node (ref "U3") (pin "7") (pinfunction "DQ3_7") (pintype "bidirectional"))
    )
    (net (code "37") (name "/DQ4B") (class "Default")
      (node (ref "R64") (pin "2") (pinfunction "2_2") (pintype "passive"))
      (node (ref "U3") (pin "8") (pinfunction "DQ4_8") (pintype "bidirectional"))
    )
    (net (code "38") (name "/DQ5B") (class "Default")
      (node (ref "R63") (pin "2") (pinfunction "2_2") (pintype "passive"))
      (node (ref "U3") (pin "10") (pinfunction "DQ5_10") (pintype "bidirectional"))
    )
    (net (code "39") (name "/DQ6B") (class "Default")
      (node (ref "R62") (pin "2") (pinfunction "2_2") (pintype "passive"))
      (node (ref "U3") (pin "11") (pinfunction "DQ6_11") (pintype "bidirectional"))
    )
    (net (code "40") (name "/DQ7B") (class "Default")
      (node (ref "R61") (pin "2") (pinfunction "2_2") (pintype "passive"))
      (node (ref "U3") (pin "13") (pinfunction "DQ7_13") (pintype "bidirectional"))
    )
    (net (code "41") (name "/DQ8B") (class "Default")
      (node (ref "R70") (pin "2") (pinfunction "2_2") (pintype "passive"))
      (node (ref "U3") (pin "54") (pinfunction "DQ8_54") (pintype "bidirectional"))
    )
    (net (code "42") (name "/DQ9B") (class "Default")
      (node (ref "R71") (pin "2") (pinfunction "2_2") (pintype "passive"))
      (node (ref "U3") (pin "56") (pinfunction "DQ9_56") (pintype "bidirectional"))
    )
    (net (code "43") (name "/DQ10B") (class "Default")
      (node (ref "R72") (pin "2") (pinfunction "2_2") (pintype "passive"))
      (node (ref "U3") (pin "57") (pinfunction "DQ10_57") (pintype "bidirectional"))
    )
    (net (code "44") (name "/DQ11B") (class "Default")
      (node (ref "R73") (pin "2") (pinfunction "2_2") (pintype "passive"))
      (node (ref "U3") (pin "59") (pinfunction "DQ11_59") (pintype "bidirectional"))
    )
    (net (code "45") (name "/DQ12B") (class "Default")
      (node (ref "R74") (pin "2") (pinfunction "2_2") (pintype "passive"))
      (node (ref "U3") (pin "60") (pinfunction "DQ12_60") (pintype "bidirectional"))
    )
    (net (code "46") (name "/DQ13B") (class "Default")
      (node (ref "R75") (pin "2") (pinfunction "2_2") (pintype "passive"))
      (node (ref "U3") (pin "62") (pinfunction "DQ13_62") (pintype "bidirectional"))
    )
    (net (code "47") (name "/DQ14B") (class "Default")
      (node (ref "R76") (pin "2") (pinfunction "2_2") (pintype "passive"))
      (node (ref "U3") (pin "63") (pinfunction "DQ14_63") (pintype "bidirectional"))
    )
    (net (code "48") (name "/DQ15B") (class "Default")
      (node (ref "U3") (pin "65") (pinfunction "DQ15_65") (pintype "bidirectional"))
      (node (ref "U4") (pin "B18") (pinfunction "B18_B18") (pintype "bidirectional"))
    )
    (net (code "49") (name "/LDM") (class "Default")
      (node (ref "U3") (pin "20") (pinfunction "LDM_20") (pintype "input"))
      (node (ref "U4") (pin "B7") (pinfunction "B7_B7") (pintype "bidirectional"))
    )
    (net (code "50") (name "/LDO") (class "Default")
      (node (ref "R10") (pin "2") (pinfunction "2_2") (pintype "passive"))
      (node (ref "R42") (pin "2") (pinfunction "2_2") (pintype "passive"))
      (node (ref "R6") (pin "1") (pinfunction "1_1") (pintype "passive"))
      (node (ref "R9") (pin "2") (pinfunction "2_2") (pintype "passive"))
    )
    (net (code "51") (name "/LDQSB") (class "Default")
      (node (ref "R60") (pin "2") (pinfunction "2_2") (pintype "passive"))
      (node (ref "R77") (pin "2") (pinfunction "2_2") (pintype "passive"))
      (node (ref "U3") (pin "16") (pinfunction "LDQS_16") (pintype "input"))
    )
    (net (code "52") (name "/LED3") (class "Default")
      (node (ref "R36") (pin "1") (pinfunction "1_1") (pintype "passive"))
      (node (ref "U4") (pin "B44") (pinfunction "B44_B44") (pintype "bidirectional"))
    )
    (net (code "53") (name "/RAS") (class "Default")
      (node (ref "U3") (pin "23") (pinfunction "~{RAS}_23") (pintype "input"))
      (node (ref "U4") (pin "A7") (pinfunction "A7_A7") (pintype "bidirectional"))
    )
    (net (code "54") (name "/RD+") (class "Default")
      (node (ref "C21") (pin "1") (pinfunction "1_1") (pintype "passive"))
      (node (ref "R28") (pin "2") (pinfunction "2_2") (pintype "passive"))
      (node (ref "T1") (pin "6") (pinfunction "RD+_6") (pintype "passive"))
      (node (ref "U4") (pin "B27") (pinfunction "B27_B27") (pintype "bidirectional"))
    )
    (net (code "55") (name "/RD-") (class "Default")
      (node (ref "C19") (pin "1") (pinfunction "1_1") (pintype "passive"))
      (node (ref "R29") (pin "2") (pinfunction "2_2") (pintype "passive"))
      (node (ref "T1") (pin "8") (pinfunction "RD-_8") (pintype "passive"))
      (node (ref "U4") (pin "A31") (pinfunction "A31_A31") (pintype "bidirectional"))
    )
    (net (code "56") (name "/RESETSW") (class "Default")
      (node (ref "C1") (pin "1") (pinfunction "1_1") (pintype "passive"))
      (node (ref "R2") (pin "2") (pinfunction "2_2") (pintype "passive"))
      (node (ref "SW1") (pin "3") (pinfunction "3_3") (pintype "passive"))
      (node (ref "U4") (pin "B48") (pinfunction "B48_B48") (pintype "bidirectional"))
    )
    (net (code "57") (name "/SPICLK") (class "Default")
      (node (ref "U2") (pin "6") (pinfunction "SCK_6") (pintype "input"))
      (node (ref "U4") (pin "B51") (pinfunction "B51_B51") (pintype "bidirectional"))
    )
    (net (code "58") (name "/SPICS") (class "Default")
      (node (ref "U2") (pin "1") (pinfunction "~{CS}_1") (pintype "input"))
      (node (ref "U4") (pin "B49") (pinfunction "B49_B49") (pintype "bidirectional"))
    )
    (net (code "59") (name "/SPIMISO") (class "Default")
      (node (ref "R19") (pin "1") (pinfunction "1_1") (pintype "passive"))
      (node (ref "R21") (pin "2") (pinfunction "2_2") (pintype "passive"))
      (node (ref "U4") (pin "B50") (pinfunction "B50_B50") (pintype "bidirectional"))
    )
    (net (code "60") (name "/SPIMOSI") (class "Default")
      (node (ref "U2") (pin "5") (pinfunction "SI/IO0_5") (pintype "bidirectional"))
      (node (ref "U4") (pin "A57") (pinfunction "A57_A57") (pintype "bidirectional"))
    )
    (net (code "61") (name "/SPISO") (class "Default")
      (node (ref "R19") (pin "2") (pinfunction "2_2") (pintype "passive"))
      (node (ref "U2") (pin "2") (pinfunction "SO/IO1_2") (pintype "bidirectional"))
    )
    (net (code "62") (name "/SPIW") (class "Default")
      (node (ref "R18") (pin "1") (pinfunction "1_1") (pintype "passive"))
      (node (ref "R20") (pin "2") (pinfunction "2_2") (pintype "passive"))
      (node (ref "U2") (pin "3") (pinfunction "~{W}/ACC/IO2_3") (pintype "bidirectional"))
    )
    (net (code "63") (name "/TD+") (class "Default")
      (node (ref "C18") (pin "1") (pinfunction "1_1") (pintype "passive"))
      (node (ref "R27") (pin "1") (pinfunction "1_1") (pintype "passive"))
      (node (ref "T1") (pin "1") (pinfunction "TD+_1") (pintype "passive"))
      (node (ref "U4") (pin "B28") (pinfunction "B28_B28") (pintype "bidirectional"))
    )
    (net (code "64") (name "/TD-") (class "Default")
      (node (ref "C20") (pin "1") (pinfunction "1_1") (pintype "passive"))
      (node (ref "R26") (pin "1") (pinfunction "1_1") (pintype "passive"))
      (node (ref "T1") (pin "3") (pinfunction "TD-_3") (pintype "passive"))
      (node (ref "U4") (pin "A32") (pinfunction "A32_A32") (pintype "bidirectional"))
    )
    (net (code "65") (name "/UDM") (class "Default")
      (node (ref "U3") (pin "47") (pinfunction "UDM_47") (pintype "input"))
      (node (ref "U4") (pin "A14") (pinfunction "A14_A14") (pintype "bidirectional"))
    )
    (net (code "66") (name "/UDQSB") (class "Default")
      (node (ref "R69") (pin "2") (pinfunction "2_2") (pintype "passive"))
      (node (ref "R78") (pin "2") (pinfunction "2_2") (pintype "passive"))
      (node (ref "U3") (pin "51") (pinfunction "UDQS_51") (pintype "input"))
    )
    (net (code "67") (name "/USBDM") (class "Default")
      (node (ref "R14") (pin "2") (pinfunction "2_2") (pintype "passive"))
      (node (ref "U4") (pin "A50") (pinfunction "A50_A50") (pintype "bidirectional"))
    )
    (net (code "68") (name "/USBDP") (class "Default")
      (node (ref "R15") (pin "2") (pinfunction "2_2") (pintype "passive"))
      (node (ref "U4") (pin "B43") (pinfunction "B43_B43") (pintype "bidirectional"))
    )
    (net (code "69") (name "/USBPOWER") (class "Default")
      (node (ref "R40") (pin "2") (pinfunction "2_2") (pintype "passive"))
      (node (ref "R8") (pin "2") (pinfunction "2_2") (pintype "passive"))
    )
    (net (code "70") (name "/VBUS") (class "Default")
      (node (ref "C11") (pin "1") (pinfunction "1_1") (pintype "passive"))
      (node (ref "C12") (pin "1") (pinfunction "1_1") (pintype "passive"))
      (node (ref "R5") (pin "2") (pinfunction "2_2") (pintype "passive"))
      (node (ref "U1") (pin "1") (pinfunction "OUT_1") (pintype "power_in"))
      (node (ref "USB2") (pin "1") (pinfunction "1_1") (pintype "passive"))
    )
    (net (code "71") (name "/WE") (class "Default")
      (node (ref "U3") (pin "21") (pinfunction "~{WE}_21") (pintype "input"))
      (node (ref "U4") (pin "A8") (pinfunction "A8_A8") (pintype "bidirectional"))
    )
    (net (code "72") (name "GND") (class "Default")
      (node (ref "ANT1") (pin "GND") (pinfunction "GND_GND") (pintype "power_in"))
      (node (ref "C1") (pin "2") (pinfunction "2_2") (pintype "passive"))
      (node (ref "C10") (pin "2") (pinfunction "2_2") (pintype "passive"))
      (node (ref "C100") (pin "2") (pinfunction "2_2") (pintype "passive"))
      (node (ref "C101") (pin "2") (pinfunction "2_2") (pintype "passive"))
      (node (ref "C102") (pin "2") (pinfunction "2_2") (pintype "passive"))
      (node (ref "C103") (pin "2") (pinfunction "2_2") (pintype "passive"))
      (node (ref "C104") (pin "2") (pinfunction "2_2") (pintype "passive"))
      (node (ref "C11") (pin "2") (pinfunction "2_2") (pintype "passive"))
      (node (ref "C12") (pin "2") (pinfunction "2_2") (pintype "passive"))
      (node (ref "C13") (pin "2") (pinfunction "2_2") (pintype "passive"))
      (node (ref "C15") (pin "1") (pinfunction "1_1") (pintype "passive"))
      (node (ref "C16") (pin "1") (pinfunction "1_1") (pintype "passive"))
      (node (ref "C17") (pin "1") (pinfunction "1_1") (pintype "passive"))
      (node (ref "C18") (pin "2") (pinfunction "2_2") (pintype "passive"))
      (node (ref "C19") (pin "2") (pinfunction "2_2") (pintype "passive"))
      (node (ref "C2") (pin "2") (pinfunction "2_2") (pintype "passive"))
      (node (ref "C20") (pin "2") (pinfunction "2_2") (pintype "passive"))
      (node (ref "C21") (pin "2") (pinfunction "2_2") (pintype "passive"))
      (node (ref "C22") (pin "2") (pinfunction "2_2") (pintype "passive"))
      (node (ref "C23") (pin "1") (pinfunction "1_1") (pintype "passive"))
      (node (ref "C24") (pin "2") (pinfunction "2_2") (pintype "passive"))
      (node (ref "C25") (pin "1") (pinfunction "1_1") (pintype "passive"))
      (node (ref "C27") (pin "1") (pinfunction "1_1") (pintype "passive"))
      (node (ref "C28") (pin "1") (pinfunction "1_1") (pintype "passive"))
      (node (ref "C31") (pin "2") (pinfunction "2_2") (pintype "passive"))
      (node (ref "C36") (pin "1") (pinfunction "1_1") (pintype "passive"))
      (node (ref "C38") (pin "2") (pinfunction "2_2") (pintype "passive"))
      (node (ref "C4") (pin "2") (pinfunction "2_2") (pintype "passive"))
      (node (ref "C41") (pin "1") (pinfunction "1_1") (pintype "passive"))
      (node (ref "C42") (pin "1") (pinfunction "1_1") (pintype "passive"))
      (node (ref "C43") (pin "1") (pinfunction "1_1") (pintype "passive"))
      (node (ref "C44") (pin "1") (pinfunction "1_1") (pintype "passive"))
      (node (ref "C45") (pin "1") (pinfunction "1_1") (pintype "passive"))
      (node (ref "C46") (pin "1") (pinfunction "1_1") (pintype "passive"))
      (node (ref "C47") (pin "2") (pinfunction "2_2") (pintype "passive"))
      (node (ref "C48") (pin "2") (pinfunction "2_2") (pintype "passive"))
      (node (ref "C5") (pin "2") (pinfunction "2_2") (pintype "passive"))
      (node (ref "C50") (pin "2") (pinfunction "2_2") (pintype "passive"))
      (node (ref "C51") (pin "1") (pinfunction "1_1") (pintype "passive"))
      (node (ref "C52") (pin "2") (pinfunction "2_2") (pintype "passive"))
      (node (ref "C53") (pin "2") (pinfunction "2_2") (pintype "passive"))
      (node (ref "C54") (pin "2") (pinfunction "2_2") (pintype "passive"))
      (node (ref "C55") (pin "1") (pinfunction "1_1") (pintype "passive"))
      (node (ref "C56") (pin "1") (pinfunction "1_1") (pintype "passive"))
      (node (ref "C57") (pin "1") (pinfunction "1_1") (pintype "passive"))
      (node (ref "C58") (pin "1") (pinfunction "1_1") (pintype "passive"))
      (node (ref "C59") (pin "1") (pinfunction "1_1") (pintype "passive"))
      (node (ref "C6") (pin "2") (pinfunction "2_2") (pintype "passive"))
      (node (ref "C60") (pin "1") (pinfunction "1_1") (pintype "passive"))
      (node (ref "C61") (pin "1") (pinfunction "1_1") (pintype "passive"))
      (node (ref "C62") (pin "2") (pinfunction "2_2") (pintype "passive"))
      (node (ref "C63") (pin "2") (pinfunction "2_2") (pintype "passive"))
      (node (ref "C65") (pin "2") (pinfunction "2_2") (pintype "passive"))
      (node (ref "C66") (pin "2") (pinfunction "2_2") (pintype "passive"))
      (node (ref "C67") (pin "2") (pinfunction "2_2") (pintype "passive"))
      (node (ref "C68") (pin "2") (pinfunction "2_2") (pintype "passive"))
      (node (ref "C69") (pin "2") (pinfunction "2_2") (pintype "passive"))
      (node (ref "C7") (pin "2") (pinfunction "2_2") (pintype "passive"))
      (node (ref "C70") (pin "2") (pinfunction "2_2") (pintype "passive"))
      (node (ref "C71") (pin "2") (pinfunction "2_2") (pintype "passive"))
      (node (ref "C72") (pin "2") (pinfunction "2_2") (pintype "passive"))
      (node (ref "C73") (pin "2") (pinfunction "2_2") (pintype "passive"))
      (node (ref "C74") (pin "2") (pinfunction "2_2") (pintype "passive"))
      (node (ref "C75") (pin "2") (pinfunction "2_2") (pintype "passive"))
      (node (ref "C76") (pin "2") (pinfunction "2_2") (pintype "passive"))
      (node (ref "C77") (pin "2") (pinfunction "2_2") (pintype "passive"))
      (node (ref "C78") (pin "2") (pinfunction "2_2") (pintype "passive"))
      (node (ref "C79") (pin "2") (pinfunction "2_2") (pintype "passive"))
      (node (ref "C8") (pin "2") (pinfunction "2_2") (pintype "passive"))
      (node (ref "C80") (pin "2") (pinfunction "2_2") (pintype "passive"))
      (node (ref "C81") (pin "2") (pinfunction "2_2") (pintype "passive"))
      (node (ref "C82") (pin "2") (pinfunction "2_2") (pintype "passive"))
      (node (ref "C83") (pin "2") (pinfunction "2_2") (pintype "passive"))
      (node (ref "C84") (pin "2") (pinfunction "2_2") (pintype "passive"))
      (node (ref "C85") (pin "2") (pinfunction "2_2") (pintype "passive"))
      (node (ref "C86") (pin "2") (pinfunction "2_2") (pintype "passive"))
      (node (ref "C87") (pin "2") (pinfunction "2_2") (pintype "passive"))
      (node (ref "C88") (pin "2") (pinfunction "2_2") (pintype "passive"))
      (node (ref "C89") (pin "2") (pinfunction "2_2") (pintype "passive"))
      (node (ref "C9") (pin "2") (pinfunction "2_2") (pintype "passive"))
      (node (ref "C90") (pin "2") (pinfunction "2_2") (pintype "passive"))
      (node (ref "C91") (pin "2") (pinfunction "2_2") (pintype "passive"))
      (node (ref "C92") (pin "2") (pinfunction "2_2") (pintype "passive"))
      (node (ref "C93") (pin "2") (pinfunction "2_2") (pintype "passive"))
      (node (ref "C94") (pin "2") (pinfunction "2_2") (pintype "passive"))
      (node (ref "C95") (pin "2") (pinfunction "2_2") (pintype "passive"))
      (node (ref "C96") (pin "2") (pinfunction "2_2") (pintype "passive"))
      (node (ref "C97") (pin "2") (pinfunction "2_2") (pintype "passive"))
      (node (ref "C98") (pin "2") (pinfunction "2_2") (pintype "passive"))
      (node (ref "C99") (pin "2") (pinfunction "2_2") (pintype "passive"))
      (node (ref "D1") (pin "1") (pinfunction "A_1") (pintype "passive"))
      (node (ref "D2") (pin "1") (pinfunction "A_1") (pintype "passive"))
      (node (ref "GND1") (pin "GND$1") (pinfunction "GND_GND$1") (pintype "power_in"))
      (node (ref "GND1") (pin "GND$2") (pinfunction "GND_GND$2") (pintype "power_in"))
      (node (ref "GND1") (pin "GND$3") (pinfunction "GND_GND$3") (pintype "power_in"))
      (node (ref "L12") (pin "2") (pinfunction "2_2") (pintype "passive"))
      (node (ref "L3") (pin "2") (pinfunction "2_2") (pintype "passive"))
      (node (ref "LM2575") (pin "2") (pinfunction "GND_2") (pintype "power_in"))
      (node (ref "R12") (pin "1") (pinfunction "1_1") (pintype "passive"))
      (node (ref "R13") (pin "1") (pinfunction "1_1") (pintype "passive"))
      (node (ref "R2") (pin "1") (pinfunction "1_1") (pintype "passive"))
      (node (ref "R20") (pin "1") (pinfunction "1_1") (pintype "passive"))
      (node (ref "R21") (pin "1") (pinfunction "1_1") (pintype "passive"))
      (node (ref "R31") (pin "1") (pinfunction "1_1") (pintype "passive"))
      (node (ref "R39") (pin "2") (pinfunction "2_2") (pintype "passive"))
      (node (ref "R4") (pin "1") (pinfunction "1_1") (pintype "passive"))
      (node (ref "R41") (pin "2") (pinfunction "2_2") (pintype "passive"))
      (node (ref "R43") (pin "2") (pinfunction "2_2") (pintype "passive"))
      (node (ref "R47") (pin "2") (pinfunction "2_2") (pintype "passive"))
      (node (ref "R6") (pin "2") (pinfunction "2_2") (pintype "passive"))
      (node (ref "R7") (pin "2") (pinfunction "2_2") (pintype "passive"))
      (node (ref "R77") (pin "1") (pinfunction "1_1") (pintype "passive"))
      (node (ref "R78") (pin "1") (pinfunction "1_1") (pintype "passive"))
      (node (ref "TP2") (pin "1") (pinfunction "PP_1") (pintype "input"))
      (node (ref "TP3") (pin "1") (pinfunction "PP_1") (pintype "input"))
      (node (ref "U1") (pin "2") (pinfunction "GND_2") (pintype "power_in"))
      (node (ref "U2") (pin "4") (pinfunction "GND_4") (pintype "power_in"))
      (node (ref "U3") (pin "12") (pinfunction "VSSQ_12") (pintype "power_in"))
      (node (ref "U3") (pin "34") (pinfunction "VSS_34") (pintype "power_in"))
      (node (ref "U3") (pin "48") (pinfunction "VSS_48") (pintype "power_in"))
      (node (ref "U3") (pin "52") (pinfunction "VSSQ_52") (pintype "power_in"))
      (node (ref "U3") (pin "58") (pinfunction "VSSQ_58") (pintype "power_in"))
      (node (ref "U3") (pin "6") (pinfunction "VSSQ_6") (pintype "power_in"))
      (node (ref "U3") (pin "64") (pinfunction "VSSQ_64") (pintype "power_in"))
      (node (ref "U3") (pin "66") (pinfunction "VSS_66") (pintype "power_in"))
      (node (ref "U4") (pin "A74") (pinfunction "A74_A74") (pintype "bidirectional"))
      (node (ref "U4") (pin "PAD") (pinfunction "PAD_PAD") (pintype "bidirectional"))
      (node (ref "USB1") (pin "GND") (pinfunction "1_GND") (pintype "passive"))
      (node (ref "USB2") (pin "4") (pinfunction "4_4") (pintype "passive"))
      (node (ref "Y1") (pin "2") (pinfunction "2_2") (pintype "passive"))
      (node (ref "Y1") (pin "4") (pinfunction "4_4") (pintype "passive"))
    )
    (net (code "73") (name "Net-(ANT1-PadRF)") (class "Default")
      (node (ref "ANT1") (pin "RF") (pinfunction "RF_RF") (pintype "passive"))
      (node (ref "C24") (pin "1") (pinfunction "1_1") (pintype "passive"))
      (node (ref "C26") (pin "1") (pinfunction "1_1") (pintype "passive"))
    )
    (net (code "74") (name "Net-(C14-Pad1)") (class "Default")
      (node (ref "C14") (pin "1") (pinfunction "1_1") (pintype "passive"))
      (node (ref "R22") (pin "1") (pinfunction "1_1") (pintype "passive"))
      (node (ref "R23") (pin "1") (pinfunction "1_1") (pintype "passive"))
      (node (ref "R24") (pin "1") (pinfunction "1_1") (pintype "passive"))
      (node (ref "R25") (pin "1") (pinfunction "1_1") (pintype "passive"))
    )
    (net (code "75") (name "Net-(C22-Pad1)") (class "Default")
      (node (ref "C22") (pin "1") (pinfunction "1_1") (pintype "passive"))
      (node (ref "R26") (pin "2") (pinfunction "2_2") (pintype "passive"))
      (node (ref "R27") (pin "2") (pinfunction "2_2") (pintype "passive"))
    )
    (net (code "76") (name "Net-(C23-Pad2)") (class "Default")
      (node (ref "C23") (pin "2") (pinfunction "2_2") (pintype "passive"))
      (node (ref "R28") (pin "1") (pinfunction "1_1") (pintype "passive"))
      (node (ref "R29") (pin "1") (pinfunction "1_1") (pintype "passive"))
    )
    (net (code "77") (name "Net-(C27-Pad2)") (class "Default")
      (node (ref "C27") (pin "2") (pinfunction "2_2") (pintype "passive"))
      (node (ref "C29") (pin "1") (pinfunction "1_1") (pintype "passive"))
      (node (ref "C32") (pin "2") (pinfunction "2_2") (pintype "passive"))
      (node (ref "L2") (pin "1") (pinfunction "1_1") (pintype "passive"))
    )
    (net (code "78") (name "Net-(C28-Pad2)") (class "Default")
      (node (ref "C28") (pin "2") (pinfunction "2_2") (pintype "passive"))
      (node (ref "C35") (pin "1") (pinfunction "1_1") (pintype "passive"))
      (node (ref "L2") (pin "2") (pinfunction "2_2") (pintype "passive"))
      (node (ref "L8") (pin "2") (pinfunction "2_2") (pintype "passive"))
    )
    (net (code "79") (name "Net-(C29-Pad2)") (class "Default")
      (node (ref "C29") (pin "2") (pinfunction "2_2") (pintype "passive"))
      (node (ref "C30") (pin "1") (pinfunction "1_1") (pintype "passive"))
      (node (ref "L3") (pin "1") (pinfunction "1_1") (pintype "passive"))
    )
    (net (code "80") (name "Net-(C30-Pad2)") (class "Default")
      (node (ref "C30") (pin "2") (pinfunction "2_2") (pintype "passive"))
      (node (ref "C33") (pin "1") (pinfunction "1_1") (pintype "passive"))
      (node (ref "L6") (pin "2") (pinfunction "2_2") (pintype "passive"))
    )
    (net (code "81") (name "Net-(C31-Pad1)") (class "Default")
      (node (ref "C31") (pin "1") (pinfunction "1_1") (pintype "passive"))
      (node (ref "C32") (pin "1") (pinfunction "1_1") (pintype "passive"))
      (node (ref "R30") (pin "1") (pinfunction "1_1") (pintype "passive"))
    )
    (net (code "82") (name "Net-(C39-Pad1)") (class "Default")
      (node (ref "C39") (pin "1") (pinfunction "1_1") (pintype "passive"))
      (node (ref "L8") (pin "1") (pinfunction "1_1") (pintype "passive"))
      (node (ref "L9") (pin "2") (pinfunction "2_2") (pintype "passive"))
    )
    (net (code "83") (name "Net-(C39-Pad2)") (class "Default")
      (node (ref "C39") (pin "2") (pinfunction "2_2") (pintype "passive"))
      (node (ref "L6") (pin "1") (pinfunction "1_1") (pintype "passive"))
      (node (ref "L7") (pin "2") (pinfunction "2_2") (pintype "passive"))
    )
    (net (code "84") (name "Net-(C56-Pad2)") (class "Default")
      (node (ref "C56") (pin "2") (pinfunction "2_2") (pintype "passive"))
      (node (ref "U4") (pin "A30") (pinfunction "A30_A30") (pintype "bidirectional"))
    )
    (net (code "85") (name "Net-(C62-Pad1)") (class "Default")
      (node (ref "C62") (pin "1") (pinfunction "1_1") (pintype "passive"))
      (node (ref "C63") (pin "1") (pinfunction "1_1") (pintype "passive"))
      (node (ref "C64") (pin "2") (pinfunction "2_2") (pintype "passive"))
      (node (ref "C70") (pin "1") (pinfunction "1_1") (pintype "passive"))
      (node (ref "C80") (pin "1") (pinfunction "1_1") (pintype "passive"))
      (node (ref "L10") (pin "1") (pinfunction "1_1") (pintype "passive"))
      (node (ref "L11") (pin "2") (pinfunction "2_2") (pintype "passive"))
      (node (ref "R37") (pin "2") (pinfunction "2_2") (pintype "passive"))
      (node (ref "R47") (pin "1") (pinfunction "1_1") (pintype "passive"))
      (node (ref "U4") (pin "A61") (pinfunction "A61_A61") (pintype "bidirectional"))
      (node (ref "U4") (pin "B40") (pinfunction "B40_B40") (pintype "bidirectional"))
      (node (ref "U4") (pin "B59") (pinfunction "B59_B59") (pintype "bidirectional"))
    )
    (net (code "86") (name "Net-(C65-Pad1)") (class "Default")
      (node (ref "C65") (pin "1") (pinfunction "1_1") (pintype "passive"))
      (node (ref "U4") (pin "B20") (pinfunction "B20_B20") (pintype "bidirectional"))
    )
    (net (code "87") (name "Net-(C71-Pad1)") (class "Default")
      (node (ref "C71") (pin "1") (pinfunction "1_1") (pintype "passive"))
      (node (ref "C72") (pin "1") (pinfunction "1_1") (pintype "passive"))
      (node (ref "U4") (pin "B39") (pinfunction "B39_B39") (pintype "bidirectional"))
    )
    (net (code "88") (name "Net-(C73-Pad1)") (class "Default")
      (node (ref "C73") (pin "1") (pinfunction "1_1") (pintype "passive"))
      (node (ref "U4") (pin "A48") (pinfunction "A48_A48") (pintype "bidirectional"))
    )
    (net (code "89") (name "Net-(C74-Pad1)") (class "Default")
      (node (ref "C74") (pin "1") (pinfunction "1_1") (pintype "passive"))
      (node (ref "U4") (pin "A49") (pinfunction "A49_A49") (pintype "bidirectional"))
    )
    (net (code "90") (name "Net-(C75-Pad1)") (class "Default")
      (node (ref "C75") (pin "1") (pinfunction "1_1") (pintype "passive"))
      (node (ref "U4") (pin "B42") (pinfunction "B42_B42") (pintype "bidirectional"))
    )
    (net (code "91") (name "Net-(C76-Pad1)") (class "Default")
      (node (ref "C76") (pin "1") (pinfunction "1_1") (pintype "passive"))
      (node (ref "U4") (pin "B45") (pinfunction "B45_B45") (pintype "bidirectional"))
    )
    (net (code "92") (name "Net-(C77-Pad1)") (class "Default")
      (node (ref "C77") (pin "1") (pinfunction "1_1") (pintype "passive"))
      (node (ref "R44") (pin "2") (pinfunction "2_2") (pintype "passive"))
      (node (ref "U4") (pin "A55") (pinfunction "A55_A55") (pintype "bidirectional"))
    )
    (net (code "93") (name "Net-(C78-Pad1)") (class "Default")
      (node (ref "C78") (pin "1") (pinfunction "1_1") (pintype "passive"))
      (node (ref "C79") (pin "1") (pinfunction "1_1") (pintype "passive"))
      (node (ref "U4") (pin "A58") (pinfunction "A58_A58") (pintype "bidirectional"))
      (node (ref "U4") (pin "B47") (pinfunction "B47_B47") (pintype "bidirectional"))
    )
    (net (code "94") (name "Net-(C81-Pad1)") (class "Default")
      (node (ref "C81") (pin "1") (pinfunction "1_1") (pintype "passive"))
      (node (ref "C86") (pin "1") (pinfunction "1_1") (pintype "passive"))
      (node (ref "C88") (pin "1") (pinfunction "1_1") (pintype "passive"))
      (node (ref "C90") (pin "1") (pinfunction "1_1") (pintype "passive"))
      (node (ref "R45") (pin "1") (pinfunction "1_1") (pintype "passive"))
      (node (ref "R46") (pin "1") (pinfunction "1_1") (pintype "passive"))
      (node (ref "U4") (pin "B55") (pinfunction "B55_B55") (pintype "bidirectional"))
      (node (ref "U4") (pin "B60") (pinfunction "B60_B60") (pintype "bidirectional"))
      (node (ref "U4") (pin "B61") (pinfunction "B61_B61") (pintype "bidirectional"))
      (node (ref "U4") (pin "B62") (pinfunction "B62_B62") (pintype "bidirectional"))
    )
    (net (code "95") (name "Net-(C82-Pad1)") (class "Default")
      (node (ref "C82") (pin "1") (pinfunction "1_1") (pintype "passive"))
      (node (ref "L11") (pin "1") (pinfunction "1_1") (pintype "passive"))
      (node (ref "U4") (pin "B56") (pinfunction "B56_B56") (pintype "bidirectional"))
    )
    (net (code "96") (name "Net-(C84-Pad1)") (class "Default")
      (node (ref "C84") (pin "1") (pinfunction "1_1") (pintype "passive"))
      (node (ref "U4") (pin "A68") (pinfunction "A68_A68") (pintype "bidirectional"))
    )
    (net (code "97") (name "Net-(C85-Pad1)") (class "Default")
      (node (ref "C85") (pin "1") (pinfunction "1_1") (pintype "passive"))
      (node (ref "U4") (pin "A70") (pinfunction "A70_A70") (pintype "bidirectional"))
    )
    (net (code "98") (name "Net-(C87-Pad1)") (class "Default")
      (node (ref "C87") (pin "1") (pinfunction "1_1") (pintype "passive"))
      (node (ref "U4") (pin "A71") (pinfunction "A71_A71") (pintype "bidirectional"))
    )
    (net (code "99") (name "Net-(C89-Pad1)") (class "Default")
      (node (ref "C89") (pin "1") (pinfunction "1_1") (pintype "passive"))
      (node (ref "U4") (pin "A72") (pinfunction "A72_A72") (pintype "bidirectional"))
    )
    (net (code "100") (name "Net-(C91-Pad1)") (class "Default")
      (node (ref "C91") (pin "1") (pinfunction "1_1") (pintype "passive"))
      (node (ref "U4") (pin "A73") (pinfunction "A73_A73") (pintype "bidirectional"))
      (node (ref "Y1") (pin "1") (pinfunction "1_1") (pintype "passive"))
    )
    (net (code "101") (name "Net-(C92-Pad1)") (class "Default")
      (node (ref "C92") (pin "1") (pinfunction "1_1") (pintype "passive"))
      (node (ref "U4") (pin "B63") (pinfunction "B63_B63") (pintype "bidirectional"))
      (node (ref "Y1") (pin "3") (pinfunction "3_3") (pintype "passive"))
    )
    (net (code "102") (name "Net-(C93-Pad1)") (class "Default")
      (node (ref "C93") (pin "1") (pinfunction "1_1") (pintype "passive"))
      (node (ref "C94") (pin "1") (pinfunction "1_1") (pintype "passive"))
      (node (ref "U4") (pin "B67") (pinfunction "B67_B67") (pintype "bidirectional"))
    )
    (net (code "103") (name "Net-(C98-Pad1)") (class "Default")
      (node (ref "C98") (pin "1") (pinfunction "1_1") (pintype "passive"))
      (node (ref "U4") (pin "A84") (pinfunction "A84_A84") (pintype "bidirectional"))
    )
    (net (code "104") (name "Net-(C99-Pad1)") (class "Default")
      (node (ref "C99") (pin "1") (pinfunction "1_1") (pintype "passive"))
      (node (ref "U4") (pin "B1") (pinfunction "B1_B1") (pintype "bidirectional"))
    )
    (net (code "105") (name "Net-(C100-Pad1)") (class "Default")
      (node (ref "C100") (pin "1") (pinfunction "1_1") (pintype "passive"))
      (node (ref "U4") (pin "A5") (pinfunction "A5_A5") (pintype "bidirectional"))
    )
    (net (code "106") (name "Net-(C101-Pad1)") (class "Default")
      (node (ref "C101") (pin "1") (pinfunction "1_1") (pintype "passive"))
      (node (ref "U4") (pin "A12") (pinfunction "A12_A12") (pintype "bidirectional"))
    )
    (net (code "107") (name "Net-(C103-Pad1)") (class "Default")
      (node (ref "C103") (pin "1") (pinfunction "1_1") (pintype "passive"))
      (node (ref "U4") (pin "A19") (pinfunction "A19_A19") (pintype "bidirectional"))
    )
    (net (code "108") (name "Net-(C104-Pad1)") (class "Default")
      (node (ref "C104") (pin "1") (pinfunction "1_1") (pintype "passive"))
      (node (ref "U4") (pin "B19") (pinfunction "B19_B19") (pintype "bidirectional"))
    )
    (net (code "109") (name "Net-(J1-Pad1)") (class "Default")
      (node (ref "J1") (pin "1") (pinfunction "1_1") (pintype "passive"))
      (node (ref "J1") (pin "2") (pinfunction "2_2") (pintype "passive"))
      (node (ref "R23") (pin "2") (pinfunction "2_2") (pintype "passive"))
    )
    (net (code "110") (name "Net-(J1-Pad4)") (class "Default")
      (node (ref "J1") (pin "4") (pinfunction "4_4") (pintype "passive"))
      (node (ref "J1") (pin "5") (pinfunction "5_5") (pintype "passive"))
      (node (ref "R22") (pin "2") (pinfunction "2_2") (pintype "passive"))
    )
    (net (code "111") (name "Net-(L10-Pad2)") (class "Default")
      (node (ref "L10") (pin "2") (pinfunction "2_2") (pintype "passive"))
      (node (ref "U4") (pin "A25") (pinfunction "A25_A25") (pintype "bidirectional"))
    )
    (net (code "112") (name "Net-(L12-Pad1)") (class "Default")
      (node (ref "L12") (pin "1") (pinfunction "1_1") (pintype "passive"))
      (node (ref "U4") (pin "A69") (pinfunction "A69_A69") (pintype "bidirectional"))
    )
    (net (code "113") (name "Net-(LED1-C)") (class "Default")
      (node (ref "LED1") (pin "K") (pinfunction "C_K") (pintype "passive"))
      (node (ref "LED2") (pin "K") (pinfunction "C_K") (pintype "passive"))
      (node (ref "R36") (pin "2") (pinfunction "2_2") (pintype "passive"))
    )
    (net (code "114") (name "Net-(LM2575-FB)") (class "Default")
      (node (ref "C3") (pin "2") (pinfunction "2_2") (pintype "passive"))
      (node (ref "LM2575") (pin "5") (pinfunction "FB_5") (pintype "passive"))
      (node (ref "R3") (pin "1") (pinfunction "1_1") (pintype "passive"))
      (node (ref "R4") (pin "2") (pinfunction "2_2") (pintype "passive"))
    )
    (net (code "115") (name "Net-(LM2575-LX)") (class "Default")
      (node (ref "L1") (pin "1") (pinfunction "1_1") (pintype "passive"))
      (node (ref "LM2575") (pin "3") (pinfunction "LX_3") (pintype "passive"))
    )
    (net (code "116") (name "Net-(Q1-E)") (class "Default")
      (node (ref "Q1") (pin "2") (pinfunction "E_2") (pintype "passive"))
      (node (ref "R35") (pin "1") (pinfunction "1_1") (pintype "passive"))
    )
    (net (code "117") (name "Net-(Q2-B)") (class "Default")
      (node (ref "Q2") (pin "1") (pinfunction "B_1") (pintype "passive"))
      (node (ref "R38") (pin "1") (pinfunction "1_1") (pintype "passive"))
      (node (ref "U4") (pin "B41") (pinfunction "B41_B41") (pintype "bidirectional"))
    )
    (net (code "118") (name "Net-(R1-Pad2)") (class "Default")
      (node (ref "R1") (pin "2") (pinfunction "2_2") (pintype "passive"))
      (node (ref "SW1") (pin "2") (pinfunction "2_2") (pintype "passive"))
    )
    (net (code "119") (name "Net-(R16-Pad1)") (class "Default")
      (node (ref "R16") (pin "1") (pinfunction "1_1") (pintype "passive"))
      (node (ref "R17") (pin "2") (pinfunction "2_2") (pintype "passive"))
    )
    (net (code "120") (name "Net-(R24-Pad2)") (class "Default")
      (node (ref "R24") (pin "2") (pinfunction "2_2") (pintype "passive"))
      (node (ref "T1") (pin "15") (pinfunction "GND_15") (pintype "power_in"))
    )
    (net (code "121") (name "Net-(R25-Pad2)") (class "Default")
      (node (ref "R25") (pin "2") (pinfunction "2_2") (pintype "passive"))
      (node (ref "T1") (pin "10") (pinfunction "GND_10") (pintype "power_in"))
    )
    (net (code "122") (name "Net-(R39-Pad1)") (class "Default")
      (node (ref "R39") (pin "1") (pinfunction "1_1") (pintype "passive"))
      (node (ref "U4") (pin "A47") (pinfunction "A47_A47") (pintype "bidirectional"))
    )
    (net (code "123") (name "Net-(R40-Pad1)") (class "Default")
      (node (ref "R40") (pin "1") (pinfunction "1_1") (pintype "passive"))
      (node (ref "U4") (pin "A52") (pinfunction "A52_A52") (pintype "bidirectional"))
    )
    (net (code "124") (name "Net-(R41-Pad1)") (class "Default")
      (node (ref "R41") (pin "1") (pinfunction "1_1") (pintype "passive"))
      (node (ref "U4") (pin "A53") (pinfunction "A53_A53") (pintype "bidirectional"))
    )
    (net (code "125") (name "Net-(R42-Pad1)") (class "Default")
      (node (ref "R42") (pin "1") (pinfunction "1_1") (pintype "passive"))
      (node (ref "U4") (pin "B46") (pinfunction "B46_B46") (pintype "bidirectional"))
    )
    (net (code "126") (name "Net-(R43-Pad1)") (class "Default")
      (node (ref "R43") (pin "1") (pinfunction "1_1") (pintype "passive"))
      (node (ref "U4") (pin "A54") (pinfunction "A54_A54") (pintype "bidirectional"))
    )
    (net (code "127") (name "Net-(R44-Pad1)") (class "Default")
      (node (ref "R44") (pin "1") (pinfunction "1_1") (pintype "passive"))
      (node (ref "U4") (pin "A56") (pinfunction "A56_A56") (pintype "bidirectional"))
    )
    (net (code "128") (name "Net-(R48-Pad1)") (class "Default")
      (node (ref "R48") (pin "1") (pinfunction "1_1") (pintype "passive"))
      (node (ref "U4") (pin "B64") (pinfunction "B64_B64") (pintype "bidirectional"))
    )
    (net (code "129") (name "Net-(R49-Pad1)") (class "Default")
      (node (ref "R49") (pin "1") (pinfunction "1_1") (pintype "passive"))
      (node (ref "U4") (pin "A75") (pinfunction "A75_A75") (pintype "bidirectional"))
    )
    (net (code "130") (name "Net-(R49-Pad2)") (class "Default")
      (node (ref "R49") (pin "2") (pinfunction "2_2") (pintype "passive"))
      (node (ref "R50") (pin "2") (pinfunction "2_2") (pintype "passive"))
      (node (ref "R51") (pin "2") (pinfunction "2_2") (pintype "passive"))
      (node (ref "R54") (pin "2") (pinfunction "2_2") (pintype "passive"))
    )
    (net (code "131") (name "Net-(R50-Pad1)") (class "Default")
      (node (ref "R50") (pin "1") (pinfunction "1_1") (pintype "passive"))
      (node (ref "U4") (pin "B65") (pinfunction "B65_B65") (pintype "bidirectional"))
    )
    (net (code "132") (name "Net-(R51-Pad1)") (class "Default")
      (node (ref "R51") (pin "1") (pinfunction "1_1") (pintype "passive"))
      (node (ref "U4") (pin "A76") (pinfunction "A76_A76") (pintype "bidirectional"))
    )
    (net (code "133") (name "Net-(R52-Pad1)") (class "Default")
      (node (ref "R52") (pin "1") (pinfunction "1_1") (pintype "passive"))
      (node (ref "U4") (pin "B66") (pinfunction "B66_B66") (pintype "bidirectional"))
    )
    (net (code "134") (name "Net-(R53-Pad1)") (class "Default")
      (node (ref "R53") (pin "1") (pinfunction "1_1") (pintype "passive"))
      (node (ref "U4") (pin "A77") (pinfunction "A77_A77") (pintype "bidirectional"))
    )
    (net (code "135") (name "Net-(R54-Pad1)") (class "Default")
      (node (ref "R54") (pin "1") (pinfunction "1_1") (pintype "passive"))
      (node (ref "U4") (pin "A78") (pinfunction "A78_A78") (pintype "bidirectional"))
    )
    (net (code "136") (name "Net-(R56-Pad1)") (class "Default")
      (node (ref "R56") (pin "1") (pinfunction "1_1") (pintype "passive"))
      (node (ref "U4") (pin "A3") (pinfunction "A3_A3") (pintype "bidirectional"))
    )
    (net (code "137") (name "Net-(R57-Pad1)") (class "Default")
      (node (ref "R57") (pin "1") (pinfunction "1_1") (pintype "passive"))
      (node (ref "U4") (pin "B2") (pinfunction "B2_B2") (pintype "bidirectional"))
    )
    (net (code "138") (name "Net-(R58-Pad1)") (class "Default")
      (node (ref "R58") (pin "1") (pinfunction "1_1") (pintype "passive"))
      (node (ref "U4") (pin "A4") (pinfunction "A4_A4") (pintype "bidirectional"))
    )
    (net (code "139") (name "Net-(R59-Pad1)") (class "Default")
      (node (ref "R59") (pin "1") (pinfunction "1_1") (pintype "passive"))
      (node (ref "U4") (pin "B3") (pinfunction "B3_B3") (pintype "bidirectional"))
    )
    (net (code "140") (name "Net-(R60-Pad1)") (class "Default")
      (node (ref "R60") (pin "1") (pinfunction "1_1") (pintype "passive"))
      (node (ref "U4") (pin "A9") (pinfunction "A9_A9") (pintype "bidirectional"))
    )
    (net (code "141") (name "Net-(R61-Pad1)") (class "Default")
      (node (ref "R61") (pin "1") (pinfunction "1_1") (pintype "passive"))
      (node (ref "U4") (pin "B8") (pinfunction "B8_B8") (pintype "bidirectional"))
    )
    (net (code "142") (name "Net-(R62-Pad1)") (class "Default")
      (node (ref "R62") (pin "1") (pinfunction "1_1") (pintype "passive"))
      (node (ref "U4") (pin "A10") (pinfunction "A10_A10") (pintype "bidirectional"))
    )
    (net (code "143") (name "Net-(R63-Pad1)") (class "Default")
      (node (ref "R63") (pin "1") (pinfunction "1_1") (pintype "passive"))
      (node (ref "U4") (pin "B9") (pinfunction "B9_B9") (pintype "bidirectional"))
    )
    (net (code "144") (name "Net-(R64-Pad1)") (class "Default")
      (node (ref "R64") (pin "1") (pinfunction "1_1") (pintype "passive"))
      (node (ref "U4") (pin "A11") (pinfunction "A11_A11") (pintype "bidirectional"))
    )
    (net (code "145") (name "Net-(R65-Pad1)") (class "Default")
      (node (ref "R65") (pin "1") (pinfunction "1_1") (pintype "passive"))
      (node (ref "U4") (pin "B10") (pinfunction "B10_B10") (pintype "bidirectional"))
    )
    (net (code "146") (name "Net-(R66-Pad1)") (class "Default")
      (node (ref "R66") (pin "1") (pinfunction "1_1") (pintype "passive"))
      (node (ref "U4") (pin "B11") (pinfunction "B11_B11") (pintype "bidirectional"))
    )
    (net (code "147") (name "Net-(R67-Pad1)") (class "Default")
      (node (ref "R67") (pin "1") (pinfunction "1_1") (pintype "passive"))
      (node (ref "U4") (pin "A13") (pinfunction "A13_A13") (pintype "bidirectional"))
    )
    (net (code "148") (name "Net-(R68-Pad1)") (class "Default")
      (node (ref "R68") (pin "1") (pinfunction "1_1") (pintype "passive"))
      (node (ref "U4") (pin "B12") (pinfunction "B12_B12") (pintype "bidirectional"))
    )
    (net (code "149") (name "Net-(R69-Pad1)") (class "Default")
      (node (ref "R69") (pin "1") (pinfunction "1_1") (pintype "passive"))
      (node (ref "U4") (pin "A15") (pinfunction "A15_A15") (pintype "bidirectional"))
    )
    (net (code "150") (name "Net-(R70-Pad1)") (class "Default")
      (node (ref "R70") (pin "1") (pinfunction "1_1") (pintype "passive"))
      (node (ref "U4") (pin "B14") (pinfunction "B14_B14") (pintype "bidirectional"))
    )
    (net (code "151") (name "Net-(R71-Pad1)") (class "Default")
      (node (ref "R71") (pin "1") (pinfunction "1_1") (pintype "passive"))
      (node (ref "U4") (pin "A16") (pinfunction "A16_A16") (pintype "bidirectional"))
    )
    (net (code "152") (name "Net-(R72-Pad1)") (class "Default")
      (node (ref "R72") (pin "1") (pinfunction "1_1") (pintype "passive"))
      (node (ref "U4") (pin "B15") (pinfunction "B15_B15") (pintype "bidirectional"))
    )
    (net (code "153") (name "Net-(R73-Pad1)") (class "Default")
      (node (ref "R73") (pin "1") (pinfunction "1_1") (pintype "passive"))
      (node (ref "U4") (pin "A17") (pinfunction "A17_A17") (pintype "bidirectional"))
    )
    (net (code "154") (name "Net-(R74-Pad1)") (class "Default")
      (node (ref "R74") (pin "1") (pinfunction "1_1") (pintype "passive"))
      (node (ref "U4") (pin "B16") (pinfunction "B16_B16") (pintype "bidirectional"))
    )
    (net (code "155") (name "Net-(R75-Pad1)") (class "Default")
      (node (ref "R75") (pin "1") (pinfunction "1_1") (pintype "passive"))
      (node (ref "U4") (pin "A18") (pinfunction "A18_A18") (pintype "bidirectional"))
    )
    (net (code "156") (name "Net-(R76-Pad1)") (class "Default")
      (node (ref "R76") (pin "1") (pinfunction "1_1") (pintype "passive"))
      (node (ref "U4") (pin "B17") (pinfunction "B17_B17") (pintype "bidirectional"))
    )
    (net (code "157") (name "Net-(SW1-SH$1)") (class "Default")
      (node (ref "SW1") (pin "S$1") (pinfunction "SH$1_S$1") (pintype "passive"))
      (node (ref "SW1") (pin "S$2") (pinfunction "SH$2_S$2") (pintype "passive"))
    )
    (net (code "158") (name "Net-(T1-RX+)") (class "Default")
      (node (ref "J1") (pin "7") (pinfunction "7_7") (pintype "passive"))
      (node (ref "T1") (pin "11") (pinfunction "RX+_11") (pintype "passive"))
    )
    (net (code "159") (name "Net-(T1-RX-)") (class "Default")
      (node (ref "J1") (pin "8") (pinfunction "8_8") (pintype "passive"))
      (node (ref "T1") (pin "9") (pinfunction "RX-_9") (pintype "passive"))
    )
    (net (code "160") (name "Net-(T1-TX+)") (class "Default")
      (node (ref "J1") (pin "3") (pinfunction "3_3") (pintype "passive"))
      (node (ref "T1") (pin "16") (pinfunction "TX+_16") (pintype "passive"))
    )
    (net (code "161") (name "Net-(T1-TX-)") (class "Default")
      (node (ref "J1") (pin "6") (pinfunction "6_6") (pintype "passive"))
      (node (ref "T1") (pin "14") (pinfunction "TX-_14") (pintype "passive"))
    )
    (net (code "162") (name "Net-(TP1V1-PP)") (class "Default")
      (node (ref "C102") (pin "1") (pinfunction "1_1") (pintype "passive"))
      (node (ref "TP1V1") (pin "1") (pinfunction "PP_1") (pintype "input"))
      (node (ref "U4") (pin "B13") (pinfunction "B13_B13") (pintype "bidirectional"))
    )
    (net (code "163") (name "Net-(TP1V2-PP)") (class "Default")
      (node (ref "C55") (pin "2") (pinfunction "2_2") (pintype "passive"))
      (node (ref "C57") (pin "2") (pinfunction "2_2") (pintype "passive"))
      (node (ref "C61") (pin "2") (pinfunction "2_2") (pintype "passive"))
      (node (ref "C66") (pin "1") (pinfunction "1_1") (pintype "passive"))
      (node (ref "C67") (pin "1") (pinfunction "1_1") (pintype "passive"))
      (node (ref "R37") (pin "1") (pinfunction "1_1") (pintype "passive"))
      (node (ref "TP1V2") (pin "1") (pinfunction "PP_1") (pintype "input"))
      (node (ref "U4") (pin "A26") (pinfunction "A26_A26") (pintype "bidirectional"))
      (node (ref "U4") (pin "B21") (pinfunction "B21_B21") (pintype "bidirectional"))
      (node (ref "U4") (pin "B26") (pinfunction "B26_B26") (pintype "bidirectional"))
      (node (ref "U4") (pin "B31") (pinfunction "B31_B31") (pintype "bidirectional"))
      (node (ref "U4") (pin "B36") (pinfunction "B36_B36") (pintype "bidirectional"))
    )
    (net (code "164") (name "Net-(TP1V3-PP)") (class "Default")
      (node (ref "C95") (pin "1") (pinfunction "1_1") (pintype "passive"))
      (node (ref "TP1V3") (pin "1") (pinfunction "PP_1") (pintype "input"))
      (node (ref "U4") (pin "B69") (pinfunction "B69_B69") (pintype "bidirectional"))
    )
    (net (code "165") (name "Net-(TPIN-PP)") (class "Default")
      (node (ref "C96") (pin "1") (pinfunction "1_1") (pintype "passive"))
      (node (ref "R55") (pin "2") (pinfunction "2_2") (pintype "passive"))
      (node (ref "TPIN") (pin "1") (pinfunction "PP_1") (pintype "input"))
      (node (ref "U4") (pin "B68") (pinfunction "B68_B68") (pintype "bidirectional"))
    )
    (net (code "166") (name "Net-(TPOUT-PP)") (class "Default")
      (node (ref "C97") (pin "1") (pinfunction "1_1") (pintype "passive"))
      (node (ref "TPOUT") (pin "1") (pinfunction "PP_1") (pintype "input"))
      (node (ref "U4") (pin "A79") (pinfunction "A79_A79") (pintype "bidirectional"))
    )
    (net (code "167") (name "Net-(U1-~{EN})") (class "Default")
      (node (ref "R11") (pin "2") (pinfunction "2_2") (pintype "passive"))
      (node (ref "R7") (pin "1") (pinfunction "1_1") (pintype "passive"))
      (node (ref "R8") (pin "1") (pinfunction "1_1") (pintype "passive"))
      (node (ref "U1") (pin "4") (pinfunction "~{EN}_4") (pintype "input"))
    )
    (net (code "168") (name "Net-(U1-~{OC})") (class "Default")
      (node (ref "R9") (pin "1") (pinfunction "1_1") (pintype "passive"))
      (node (ref "U1") (pin "3") (pinfunction "~{OC}_3") (pintype "open_collector"))
    )
    (net (code "169") (name "Net-(U2-~{HOLD}{slash}IO3)") (class "Default")
      (node (ref "R16") (pin "2") (pinfunction "2_2") (pintype "passive"))
      (node (ref "U2") (pin "7") (pinfunction "~{HOLD}/IO3_7") (pintype "bidirectional"))
    )
    (net (code "170") (name "Net-(U3-VREF)") (class "Default")
      (node (ref "C51") (pin "2") (pinfunction "2_2") (pintype "passive"))
      (node (ref "C54") (pin "1") (pinfunction "1_1") (pintype "passive"))
      (node (ref "R31") (pin "2") (pinfunction "2_2") (pintype "passive"))
      (node (ref "R32") (pin "1") (pinfunction "1_1") (pintype "passive"))
      (node (ref "U3") (pin "49") (pinfunction "VREF_49") (pintype "power_in"))
    )
    (net (code "171") (name "SHIELD") (class "Default")
      (node (ref "C10") (pin "1") (pinfunction "1_1") (pintype "passive"))
      (node (ref "C14") (pin "2") (pinfunction "2_2") (pintype "passive"))
      (node (ref "C15") (pin "2") (pinfunction "2_2") (pintype "passive"))
      (node (ref "J1") (pin "S$1") (pinfunction "SHIELD_S$1") (pintype "passive"))
      (node (ref "J1") (pin "S$2") (pinfunction "SHIELD_S$2") (pintype "passive"))
      (node (ref "USB1") (pin "P$1") (pinfunction "M0_P$1") (pintype "passive"))
      (node (ref "USB1") (pin "P$2") (pinfunction "M7_P$2") (pintype "passive"))
      (node (ref "USB1") (pin "S$1") (pinfunction "M1_S$1") (pintype "passive"))
      (node (ref "USB1") (pin "S$2") (pinfunction "M2_S$2") (pintype "passive"))
      (node (ref "USB1") (pin "S$3") (pinfunction "M3_S$3") (pintype "passive"))
      (node (ref "USB1") (pin "S$4") (pinfunction "M4_S$4") (pintype "passive"))
      (node (ref "USB1") (pin "S$5") (pinfunction "M5_S$5") (pintype "passive"))
      (node (ref "USB1") (pin "S$6") (pinfunction "M6_S$6") (pintype "passive"))
      (node (ref "USB2") (pin "S$1") (pinfunction "M1_S$1") (pintype "passive"))
      (node (ref "USB2") (pin "S$2") (pinfunction "M2_S$2") (pintype "passive"))
    )
    (net (code "172") (name "VDD") (class "Default")
      (node (ref "C41") (pin "2") (pinfunction "2_2") (pintype "passive"))
      (node (ref "C42") (pin "2") (pinfunction "2_2") (pintype "passive"))
      (node (ref "C43") (pin "2") (pinfunction "2_2") (pintype "passive"))
      (node (ref "C44") (pin "2") (pinfunction "2_2") (pintype "passive"))
      (node (ref "C45") (pin "2") (pinfunction "2_2") (pintype "passive"))
      (node (ref "C46") (pin "2") (pinfunction "2_2") (pintype "passive"))
      (node (ref "C47") (pin "1") (pinfunction "1_1") (pintype "passive"))
      (node (ref "C48") (pin "1") (pinfunction "1_1") (pintype "passive"))
      (node (ref "C50") (pin "1") (pinfunction "1_1") (pintype "passive"))
      (node (ref "Q1") (pin "3") (pinfunction "C_3") (pintype "passive"))
      (node (ref "R32") (pin "2") (pinfunction "2_2") (pintype "passive"))
      (node (ref "TP4") (pin "1") (pinfunction "PP_1") (pintype "input"))
      (node (ref "U3") (pin "1") (pinfunction "VDD_1") (pintype "power_in"))
      (node (ref "U3") (pin "15") (pinfunction "VDDQ_15") (pintype "power_in"))
      (node (ref "U3") (pin "18") (pinfunction "VDD_18") (pintype "power_in"))
      (node (ref "U3") (pin "3") (pinfunction "VDDQ_3") (pintype "power_in"))
      (node (ref "U3") (pin "33") (pinfunction "VDD_33") (pintype "power_in"))
      (node (ref "U3") (pin "55") (pinfunction "VDDQ_55") (pintype "power_in"))
      (node (ref "U3") (pin "61") (pinfunction "VDDQ_61") (pintype "power_in"))
      (node (ref "U3") (pin "9") (pinfunction "VDDQ_9") (pintype "power_in"))
    )
    (net (code "173") (name "unconnected-(SW1-Pad1)") (class "Default")
      (node (ref "SW1") (pin "1") (pinfunction "1_1") (pintype "passive"))
    )
    (net (code "174") (name "unconnected-(T1-NC-Pad4)") (class "Default")
      (node (ref "T1") (pin "4") (pinfunction "NC_4") (pintype "no_connect"))
    )
    (net (code "175") (name "unconnected-(T1-NC-Pad5)") (class "Default")
      (node (ref "T1") (pin "5") (pinfunction "NC_5") (pintype "no_connect"))
    )
    (net (code "176") (name "unconnected-(T1-NC-Pad12)") (class "Default")
      (node (ref "T1") (pin "12") (pinfunction "NC_12") (pintype "no_connect"))
    )
    (net (code "177") (name "unconnected-(T1-NC-Pad13)") (class "Default")
      (node (ref "T1") (pin "13") (pinfunction "NC_13") (pintype "no_connect"))
    )
    (net (code "178") (name "unconnected-(U3-NC-Pad14)") (class "Default")
      (node (ref "U3") (pin "14") (pinfunction "NC_14") (pintype "no_connect"))
    )
    (net (code "179") (name "unconnected-(U3-NC-Pad17)") (class "Default")
      (node (ref "U3") (pin "17") (pinfunction "NC_17") (pintype "no_connect"))
    )
    (net (code "180") (name "unconnected-(U3-NC-Pad19)") (class "Default")
      (node (ref "U3") (pin "19") (pinfunction "NC_19") (pintype "no_connect"))
    )
    (net (code "181") (name "unconnected-(U3-NC-Pad25)") (class "Default")
      (node (ref "U3") (pin "25") (pinfunction "NC_25") (pintype "no_connect"))
    )
    (net (code "182") (name "unconnected-(U3-NC-Pad43)") (class "Default")
      (node (ref "U3") (pin "43") (pinfunction "NC_43") (pintype "no_connect"))
    )
    (net (code "183") (name "unconnected-(U3-NC-Pad50)") (class "Default")
      (node (ref "U3") (pin "50") (pinfunction "NC_50") (pintype "no_connect"))
    )
    (net (code "184") (name "unconnected-(U3-NC-Pad53)") (class "Default")
      (node (ref "U3") (pin "53") (pinfunction "NC_53") (pintype "no_connect"))
    )
    (net (code "185") (name "unconnected-(U4-PadA27)") (class "Default")
      (node (ref "U4") (pin "A27") (pinfunction "A27_A27") (pintype "bidirectional"))
    )
    (net (code "186") (name "unconnected-(U4-PadA28)") (class "Default")
      (node (ref "U4") (pin "A28") (pinfunction "A28_A28") (pintype "bidirectional"))
    )
    (net (code "187") (name "unconnected-(U4-PadA29)") (class "Default")
      (node (ref "U4") (pin "A29") (pinfunction "A29_A29") (pintype "bidirectional"))
    )
    (net (code "188") (name "unconnected-(U4-PadA34)") (class "Default")
      (node (ref "U4") (pin "A34") (pinfunction "A34_A34") (pintype "bidirectional"))
    )
    (net (code "189") (name "unconnected-(U4-PadA35)") (class "Default")
      (node (ref "U4") (pin "A35") (pinfunction "A35_A35") (pintype "bidirectional"))
    )
    (net (code "190") (name "unconnected-(U4-PadA36)") (class "Default")
      (node (ref "U4") (pin "A36") (pinfunction "A36_A36") (pintype "bidirectional"))
    )
    (net (code "191") (name "unconnected-(U4-PadA37)") (class "Default")
      (node (ref "U4") (pin "A37") (pinfunction "A37_A37") (pintype "bidirectional"))
    )
    (net (code "192") (name "unconnected-(U4-PadA39)") (class "Default")
      (node (ref "U4") (pin "A39") (pinfunction "A39_A39") (pintype "bidirectional"))
    )
    (net (code "193") (name "unconnected-(U4-PadA40)") (class "Default")
      (node (ref "U4") (pin "A40") (pinfunction "A40_A40") (pintype "bidirectional"))
    )
    (net (code "194") (name "unconnected-(U4-PadA41)") (class "Default")
      (node (ref "U4") (pin "A41") (pinfunction "A41_A41") (pintype "bidirectional"))
    )
    (net (code "195") (name "unconnected-(U4-PadA42)") (class "Default")
      (node (ref "U4") (pin "A42") (pinfunction "A42_A42") (pintype "bidirectional"))
    )
    (net (code "196") (name "unconnected-(U4-PadA51)") (class "Default")
      (node (ref "U4") (pin "A51") (pinfunction "A51_A51") (pintype "bidirectional"))
    )
    (net (code "197") (name "unconnected-(U4-PadA59)") (class "Default")
      (node (ref "U4") (pin "A59") (pinfunction "A59_A59") (pintype "bidirectional"))
    )
    (net (code "198") (name "unconnected-(U4-PadA60)") (class "Default")
      (node (ref "U4") (pin "A60") (pinfunction "A60_A60") (pintype "bidirectional"))
    )
    (net (code "199") (name "unconnected-(U4-PadB22)") (class "Default")
      (node (ref "U4") (pin "B22") (pinfunction "B22_B22") (pintype "bidirectional"))
    )
    (net (code "200") (name "unconnected-(U4-PadB23)") (class "Default")
      (node (ref "U4") (pin "B23") (pinfunction "B23_B23") (pintype "bidirectional"))
    )
    (net (code "201") (name "unconnected-(U4-PadB24)") (class "Default")
      (node (ref "U4") (pin "B24") (pinfunction "B24_B24") (pintype "bidirectional"))
    )
    (net (code "202") (name "unconnected-(U4-PadB25)") (class "Default")
      (node (ref "U4") (pin "B25") (pinfunction "B25_B25") (pintype "bidirectional"))
    )
    (net (code "203") (name "unconnected-(U4-PadB29)") (class "Default")
      (node (ref "U4") (pin "B29") (pinfunction "B29_B29") (pintype "bidirectional"))
    )
    (net (code "204") (name "unconnected-(U4-PadB30)") (class "Default")
      (node (ref "U4") (pin "B30") (pinfunction "B30_B30") (pintype "bidirectional"))
    )
    (net (code "205") (name "unconnected-(U4-PadB32)") (class "Default")
      (node (ref "U4") (pin "B32") (pinfunction "B32_B32") (pintype "bidirectional"))
    )
    (net (code "206") (name "unconnected-(U4-PadB33)") (class "Default")
      (node (ref "U4") (pin "B33") (pinfunction "B33_B33") (pintype "bidirectional"))
    )
    (net (code "207") (name "unconnected-(U4-PadB34)") (class "Default")
      (node (ref "U4") (pin "B34") (pinfunction "B34_B34") (pintype "bidirectional"))
    )
    (net (code "208") (name "unconnected-(U4-PadB35)") (class "Default")
      (node (ref "U4") (pin "B35") (pinfunction "B35_B35") (pintype "bidirectional"))
    )
    (net (code "209") (name "unconnected-(U4-PadB37)") (class "Default")
      (node (ref "U4") (pin "B37") (pinfunction "B37_B37") (pintype "bidirectional"))
    )
    (net (code "210") (name "unconnected-(U4-PadB38)") (class "Default")
      (node (ref "U4") (pin "B38") (pinfunction "B38_B38") (pintype "bidirectional"))
    )
    (net (code "211") (name "unconnected-(U4-PadB52)") (class "Default")
      (node (ref "U4") (pin "B52") (pinfunction "B52_B52") (pintype "bidirectional"))
    )
    (net (code "212") (name "unconnected-(U4-PadB53)") (class "Default")
      (node (ref "U4") (pin "B53") (pinfunction "B53_B53") (pintype "bidirectional"))
    )
    (net (code "213") (name "unconnected-(U4-PadB54)") (class "Default")
      (node (ref "U4") (pin "B54") (pinfunction "B54_B54") (pintype "bidirectional"))
    )
    (net (code "214") (name "unconnected-(U4-PadB71)") (class "Default")
      (node (ref "U4") (pin "B71") (pinfunction "B71_B71") (pintype "bidirectional"))
    )
    (net (code "215") (name "unconnected-(USB1-2-PadD-)") (class "Default")
      (node (ref "USB1") (pin "D-") (pinfunction "2_D-") (pintype "passive"))
    )
    (net (code "216") (name "unconnected-(USB1-3-PadD+)") (class "Default")
      (node (ref "USB1") (pin "D+") (pinfunction "3_D+") (pintype "passive"))
    )
    (net (code "217") (name "unconnected-(USB1-4-PadID)") (class "Default")
      (node (ref "USB1") (pin "ID") (pinfunction "4_ID") (pintype "passive"))
    )
  )
)
